# ADC_Power_supply.net
KiCad netlist of a schematic drawn in Altium Designer
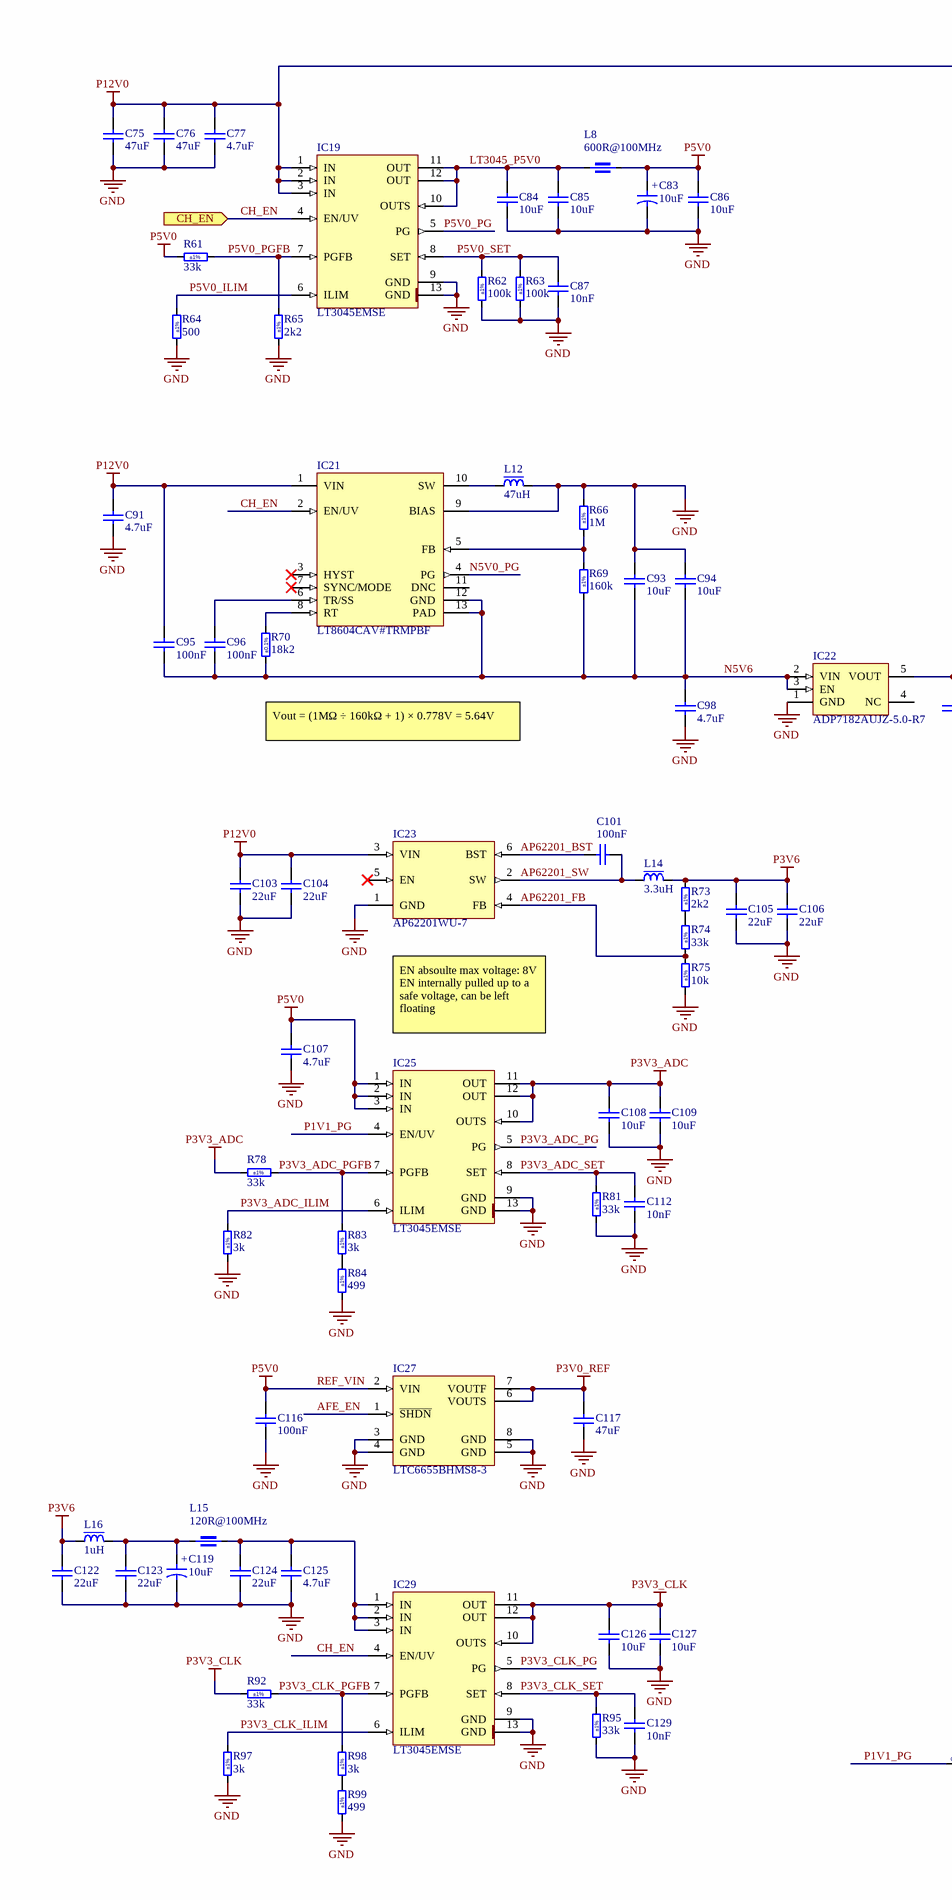
[diagram p0: ADC_Power_supply.SchDoc, left]
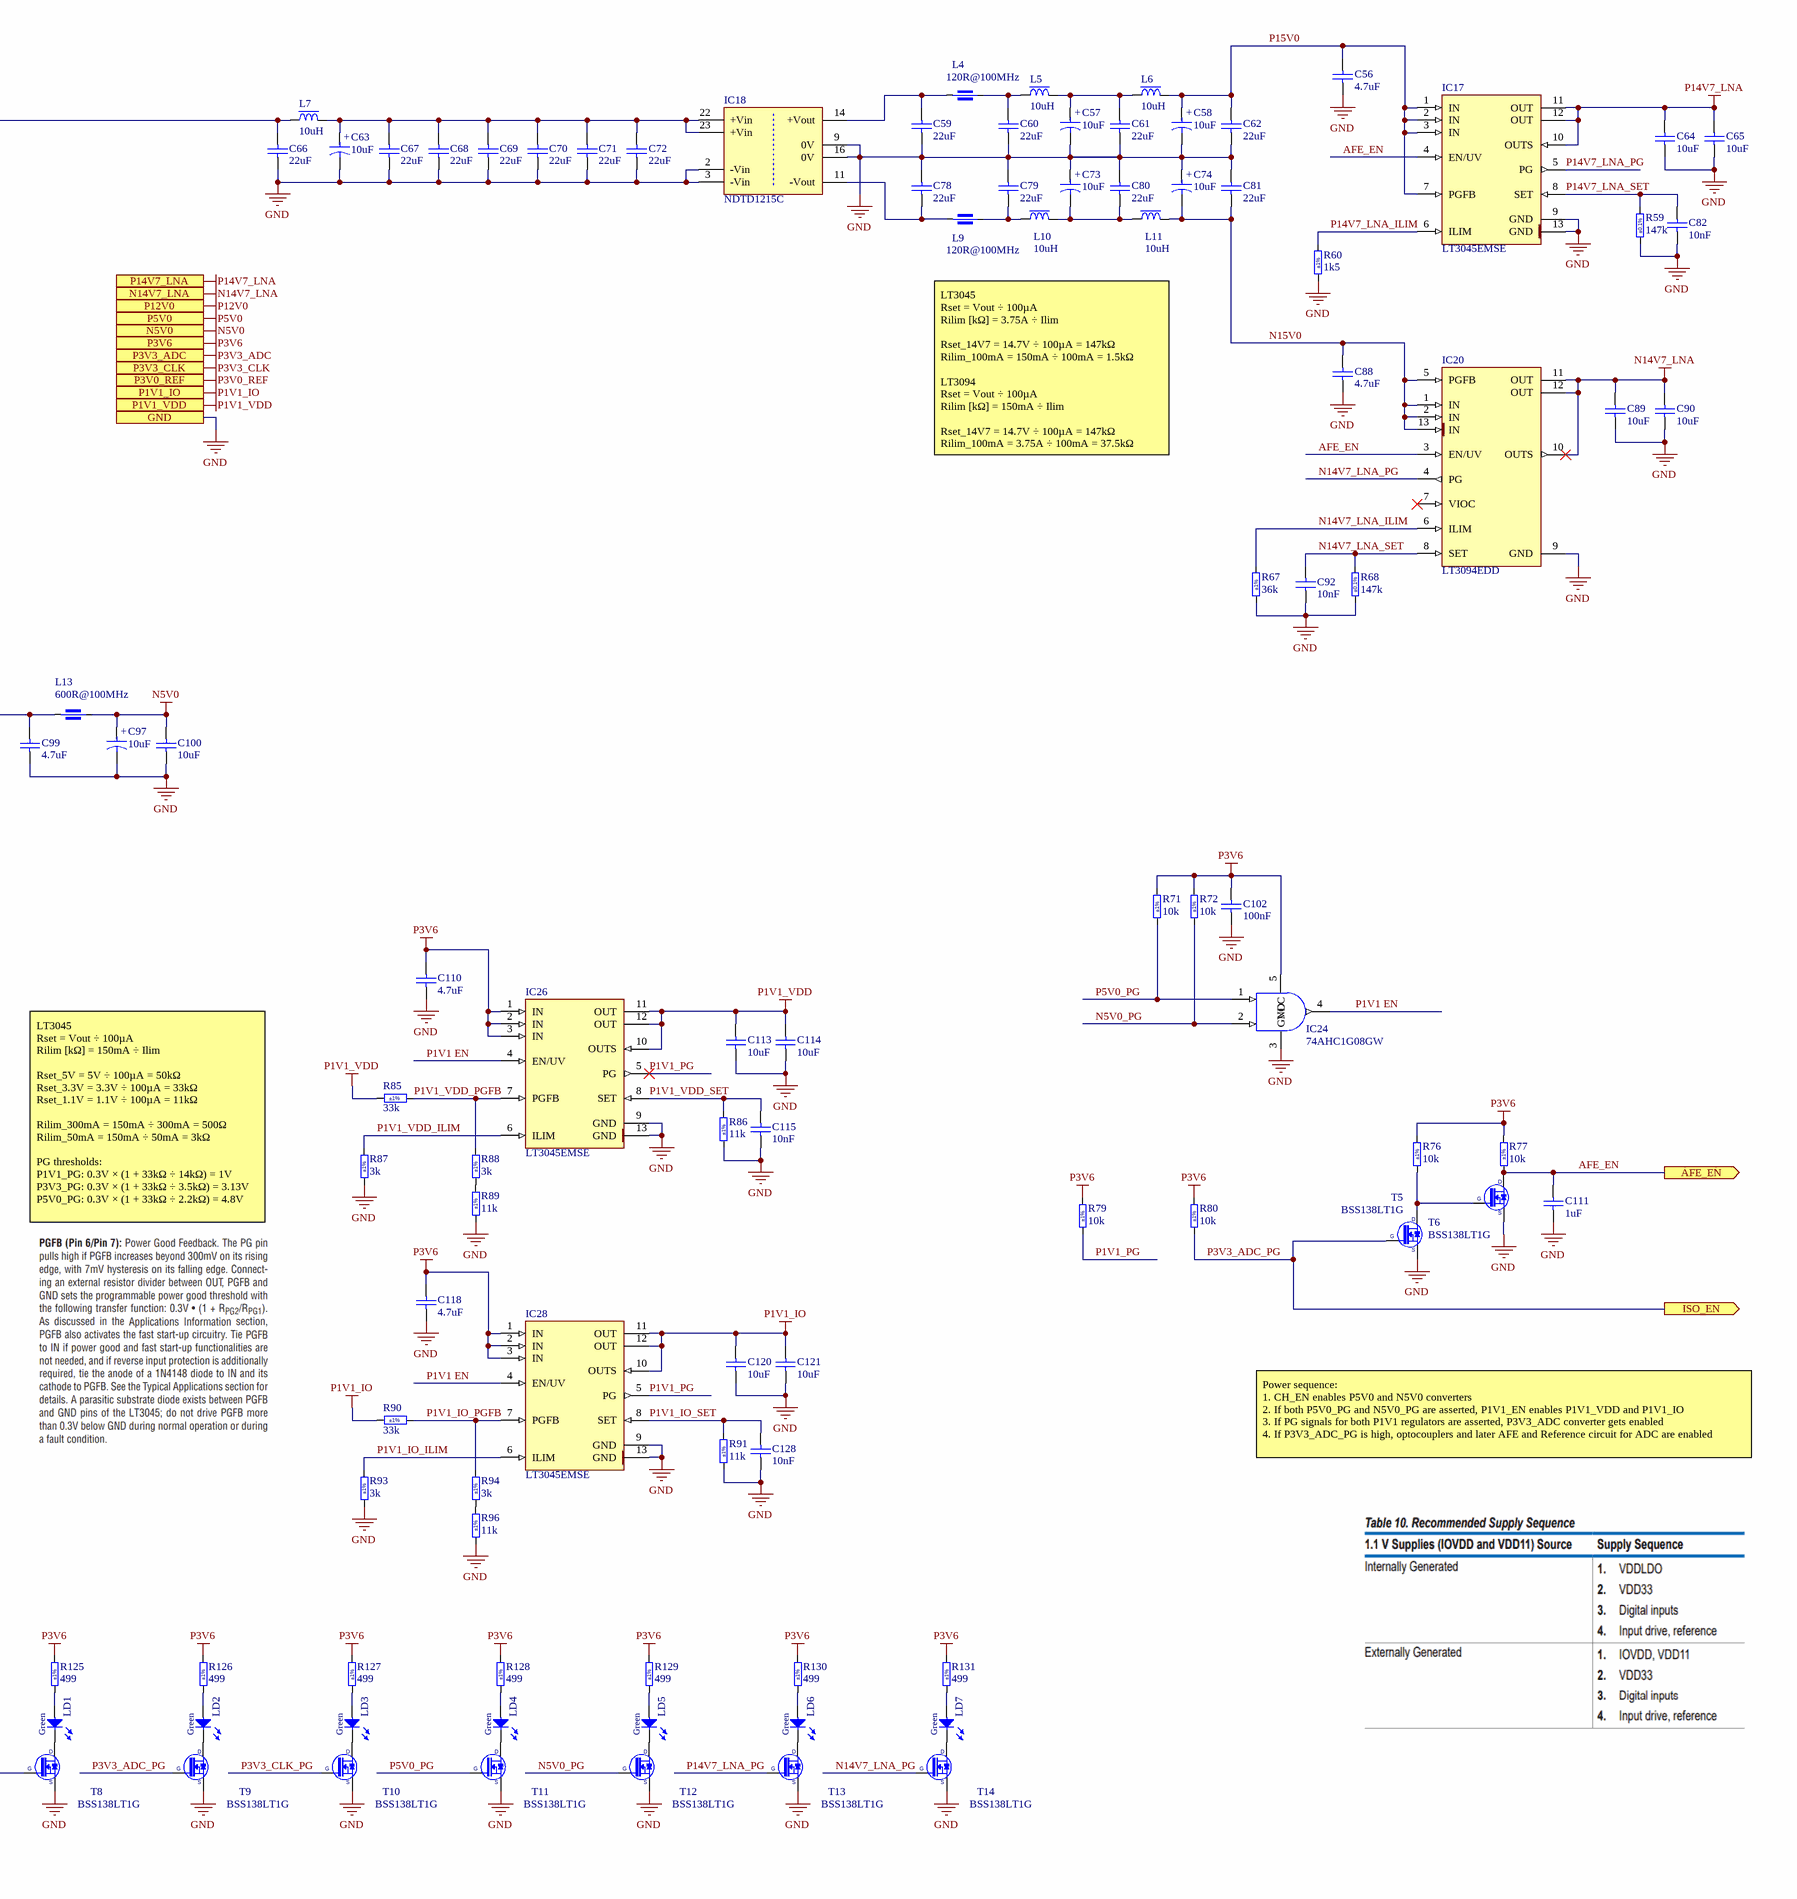
[diagram p1: ADC_Power_supply.SchDoc, right]

(export (version "E")
  (design (tool "Eeschema 10.0.6"))
  (components
    (comp (ref "C56")
      (value "4.7uF")
      (footprint "CAPC1608X90N")
      (description "Non-polarised capacitor")
      (fields
        (field (name "PART NUMBER") "CC0603_4.7UF_25V_10%_X5R")
        (field (name "VOLTAGE") "25V")
        (field (name "AUTHOR") "CERN DEM JLC")
      )
      (libsource (lib "Capacitors") (part "Capacitor - non polarized"))
    )
    (comp (ref "C57")
      (value "10uF")
      (footprint "CAPMP3216X180N")
      (description "Polarised capacitor")
      (fields
        (field (name "PART NUMBER") "CTE3216-18_10UF_16V_20%_AVX_TCJ")
        (field (name "VOLTAGE") "16V")
        (field (name "AUTHOR") "CERN DEM JLC")
      )
      (libsource (lib "Capacitors") (part "Capacitor - polarized"))
    )
    (comp (ref "C58")
      (value "10uF")
      (footprint "CAPMP3216X180N")
      (description "Polarised capacitor")
      (fields
        (field (name "PART NUMBER") "CTE3216-18_10UF_16V_20%_AVX_TCJ")
        (field (name "VOLTAGE") "16V")
        (field (name "AUTHOR") "CERN DEM JLC")
      )
      (libsource (lib "Capacitors") (part "Capacitor - polarized"))
    )
    (comp (ref "C59")
      (value "22uF")
      (footprint "CAPC2012X135N")
      (description "Non-polarised capacitor")
      (fields
        (field (name "PART NUMBER") "CC0805_22UF_16V_10%_X5R")
        (field (name "VOLTAGE") "16V")
        (field (name "AUTHOR") "CERN DEM JLC")
      )
      (libsource (lib "Capacitors") (part "Capacitor - non polarized"))
    )
    (comp (ref "C60")
      (value "22uF")
      (footprint "CAPC2012X135N")
      (description "Non-polarised capacitor")
      (fields
        (field (name "PART NUMBER") "CC0805_22UF_16V_10%_X5R")
        (field (name "VOLTAGE") "16V")
        (field (name "AUTHOR") "CERN DEM JLC")
      )
      (libsource (lib "Capacitors") (part "Capacitor - non polarized"))
    )
    (comp (ref "C61")
      (value "22uF")
      (footprint "CAPC2012X135N")
      (description "Non-polarised capacitor")
      (fields
        (field (name "PART NUMBER") "CC0805_22UF_16V_10%_X5R")
        (field (name "VOLTAGE") "16V")
        (field (name "AUTHOR") "CERN DEM JLC")
      )
      (libsource (lib "Capacitors") (part "Capacitor - non polarized"))
    )
    (comp (ref "C62")
      (value "22uF")
      (footprint "CAPC2012X135N")
      (description "Non-polarised capacitor")
      (fields
        (field (name "PART NUMBER") "CC0805_22UF_16V_10%_X5R")
        (field (name "VOLTAGE") "16V")
        (field (name "AUTHOR") "CERN DEM JLC")
      )
      (libsource (lib "Capacitors") (part "Capacitor - non polarized"))
    )
    (comp (ref "C63")
      (value "10uF")
      (footprint "CAPMP3216X180N")
      (description "Polarised capacitor")
      (fields
        (field (name "PART NUMBER") "CTE3216-18_10UF_16V_20%_AVX_TCJ")
        (field (name "VOLTAGE") "16V")
        (field (name "AUTHOR") "CERN DEM JLC")
      )
      (libsource (lib "Capacitors") (part "Capacitor - polarized"))
    )
    (comp (ref "C64")
      (value "10uF")
      (footprint "CAPC2012X95N")
      (description "Non-polarised capacitor")
      (fields
        (field (name "PART NUMBER") "CC0805_10UF_25V_10%_X5R")
        (field (name "VOLTAGE") "25V")
        (field (name "AUTHOR") "CERN DEM JLC")
      )
      (libsource (lib "Capacitors") (part "Capacitor - non polarized"))
    )
    (comp (ref "C65")
      (value "10uF")
      (footprint "CAPC2012X95N")
      (description "Non-polarised capacitor")
      (fields
        (field (name "PART NUMBER") "CC0805_10UF_25V_10%_X5R")
        (field (name "VOLTAGE") "25V")
        (field (name "AUTHOR") "CERN DEM JLC")
      )
      (libsource (lib "Capacitors") (part "Capacitor - non polarized"))
    )
    (comp (ref "C66")
      (value "22uF")
      (footprint "CAPC2012X135N")
      (description "Non-polarised capacitor")
      (fields
        (field (name "PART NUMBER") "CC0805_22UF_16V_10%_X5R")
        (field (name "VOLTAGE") "16V")
        (field (name "AUTHOR") "CERN DEM JLC")
      )
      (libsource (lib "Capacitors") (part "Capacitor - non polarized"))
    )
    (comp (ref "C67")
      (value "22uF")
      (footprint "CAPC2012X135N")
      (description "Non-polarised capacitor")
      (fields
        (field (name "PART NUMBER") "CC0805_22UF_16V_10%_X5R")
        (field (name "VOLTAGE") "16V")
        (field (name "AUTHOR") "CERN DEM JLC")
      )
      (libsource (lib "Capacitors") (part "Capacitor - non polarized"))
    )
    (comp (ref "C68")
      (value "22uF")
      (footprint "CAPC2012X135N")
      (description "Non-polarised capacitor")
      (fields
        (field (name "PART NUMBER") "CC0805_22UF_16V_10%_X5R")
        (field (name "VOLTAGE") "16V")
        (field (name "AUTHOR") "CERN DEM JLC")
      )
      (libsource (lib "Capacitors") (part "Capacitor - non polarized"))
    )
    (comp (ref "C69")
      (value "22uF")
      (footprint "CAPC2012X135N")
      (description "Non-polarised capacitor")
      (fields
        (field (name "PART NUMBER") "CC0805_22UF_16V_10%_X5R")
        (field (name "VOLTAGE") "16V")
        (field (name "AUTHOR") "CERN DEM JLC")
      )
      (libsource (lib "Capacitors") (part "Capacitor - non polarized"))
    )
    (comp (ref "C70")
      (value "22uF")
      (footprint "CAPC2012X135N")
      (description "Non-polarised capacitor")
      (fields
        (field (name "PART NUMBER") "CC0805_22UF_16V_10%_X5R")
        (field (name "VOLTAGE") "16V")
        (field (name "AUTHOR") "CERN DEM JLC")
      )
      (libsource (lib "Capacitors") (part "Capacitor - non polarized"))
    )
    (comp (ref "C71")
      (value "22uF")
      (footprint "CAPC2012X135N")
      (description "Non-polarised capacitor")
      (fields
        (field (name "PART NUMBER") "CC0805_22UF_16V_10%_X5R")
        (field (name "VOLTAGE") "16V")
        (field (name "AUTHOR") "CERN DEM JLC")
      )
      (libsource (lib "Capacitors") (part "Capacitor - non polarized"))
    )
    (comp (ref "C72")
      (value "22uF")
      (footprint "CAPC2012X135N")
      (description "Non-polarised capacitor")
      (fields
        (field (name "PART NUMBER") "CC0805_22UF_16V_10%_X5R")
        (field (name "VOLTAGE") "16V")
        (field (name "AUTHOR") "CERN DEM JLC")
      )
      (libsource (lib "Capacitors") (part "Capacitor - non polarized"))
    )
    (comp (ref "C73")
      (value "10uF")
      (footprint "CAPMP3216X180N")
      (description "Polarised capacitor")
      (fields
        (field (name "PART NUMBER") "CTE3216-18_10UF_16V_20%_AVX_TCJ")
        (field (name "VOLTAGE") "16V")
        (field (name "AUTHOR") "CERN DEM JLC")
      )
      (libsource (lib "Capacitors") (part "Capacitor - polarized"))
    )
    (comp (ref "C74")
      (value "10uF")
      (footprint "CAPMP3216X180N")
      (description "Polarised capacitor")
      (fields
        (field (name "PART NUMBER") "CTE3216-18_10UF_16V_20%_AVX_TCJ")
        (field (name "VOLTAGE") "16V")
        (field (name "AUTHOR") "CERN DEM JLC")
      )
      (libsource (lib "Capacitors") (part "Capacitor - polarized"))
    )
    (comp (ref "C75")
      (value "47uF")
      (footprint "CAPC3216X180N")
      (description "Non-polarised capacitor")
      (fields
        (field (name "PART NUMBER") "CC1206_47UF_25V_20%_X5R")
        (field (name "VOLTAGE") "25V")
        (field (name "AUTHOR") "CERN DEM JLC")
      )
      (libsource (lib "Capacitors") (part "Capacitor - non polarized"))
    )
    (comp (ref "C76")
      (value "47uF")
      (footprint "CAPC3216X180N")
      (description "Non-polarised capacitor")
      (fields
        (field (name "PART NUMBER") "CC1206_47UF_25V_20%_X5R")
        (field (name "VOLTAGE") "25V")
        (field (name "AUTHOR") "CERN DEM JLC")
      )
      (libsource (lib "Capacitors") (part "Capacitor - non polarized"))
    )
    (comp (ref "C77")
      (value "4.7uF")
      (footprint "CAPC1608X90N")
      (description "Non-polarised capacitor")
      (fields
        (field (name "PART NUMBER") "CC0603_4.7UF_25V_10%_X5R")
        (field (name "VOLTAGE") "25V")
        (field (name "AUTHOR") "CERN DEM JLC")
      )
      (libsource (lib "Capacitors") (part "Capacitor - non polarized"))
    )
    (comp (ref "C78")
      (value "22uF")
      (footprint "CAPC2012X135N")
      (description "Non-polarised capacitor")
      (fields
        (field (name "PART NUMBER") "CC0805_22UF_16V_10%_X5R")
        (field (name "VOLTAGE") "16V")
        (field (name "AUTHOR") "CERN DEM JLC")
      )
      (libsource (lib "Capacitors") (part "Capacitor - non polarized"))
    )
    (comp (ref "C79")
      (value "22uF")
      (footprint "CAPC2012X135N")
      (description "Non-polarised capacitor")
      (fields
        (field (name "PART NUMBER") "CC0805_22UF_16V_10%_X5R")
        (field (name "VOLTAGE") "16V")
        (field (name "AUTHOR") "CERN DEM JLC")
      )
      (libsource (lib "Capacitors") (part "Capacitor - non polarized"))
    )
    (comp (ref "C80")
      (value "22uF")
      (footprint "CAPC2012X135N")
      (description "Non-polarised capacitor")
      (fields
        (field (name "PART NUMBER") "CC0805_22UF_16V_10%_X5R")
        (field (name "VOLTAGE") "16V")
        (field (name "AUTHOR") "CERN DEM JLC")
      )
      (libsource (lib "Capacitors") (part "Capacitor - non polarized"))
    )
    (comp (ref "C81")
      (value "22uF")
      (footprint "CAPC2012X135N")
      (description "Non-polarised capacitor")
      (fields
        (field (name "PART NUMBER") "CC0805_22UF_16V_10%_X5R")
        (field (name "VOLTAGE") "16V")
        (field (name "AUTHOR") "CERN DEM JLC")
      )
      (libsource (lib "Capacitors") (part "Capacitor - non polarized"))
    )
    (comp (ref "C82")
      (value "10nF")
      (footprint "CAPC1005X55N")
      (description "Non-polarised capacitor")
      (fields
        (field (name "PART NUMBER") "CC0402_10NF_16V_10%_X7R")
        (field (name "VOLTAGE") "16V")
        (field (name "AUTHOR") "CERN DEM JLC")
      )
      (libsource (lib "Capacitors") (part "Capacitor - non polarized"))
    )
    (comp (ref "C83")
      (value "10uF")
      (footprint "CAPMP3216X180N")
      (description "Polarised capacitor")
      (fields
        (field (name "PART NUMBER") "CTE3216-18_10UF_10V_10%_LESR1800")
        (field (name "VOLTAGE") "10V")
        (field (name "AUTHOR") "CERN DEM JLC")
      )
      (libsource (lib "Capacitors") (part "Capacitor - polarized"))
    )
    (comp (ref "C84")
      (value "10uF")
      (footprint "CAPC2012X95N")
      (description "Non-polarised capacitor")
      (fields
        (field (name "PART NUMBER") "CC0805_10UF_25V_10%_X5R")
        (field (name "VOLTAGE") "25V")
        (field (name "AUTHOR") "CERN DEM JLC")
      )
      (libsource (lib "Capacitors") (part "Capacitor - non polarized"))
    )
    (comp (ref "C85")
      (value "10uF")
      (footprint "CAPC2012X95N")
      (description "Non-polarised capacitor")
      (fields
        (field (name "PART NUMBER") "CC0805_10UF_25V_10%_X5R")
        (field (name "VOLTAGE") "25V")
        (field (name "AUTHOR") "CERN DEM JLC")
      )
      (libsource (lib "Capacitors") (part "Capacitor - non polarized"))
    )
    (comp (ref "C86")
      (value "10uF")
      (footprint "CAPC2012X95N")
      (description "Non-polarised capacitor")
      (fields
        (field (name "PART NUMBER") "CC0805_10UF_25V_10%_X5R")
        (field (name "VOLTAGE") "25V")
        (field (name "AUTHOR") "CERN DEM JLC")
      )
      (libsource (lib "Capacitors") (part "Capacitor - non polarized"))
    )
    (comp (ref "C87")
      (value "10nF")
      (footprint "CAPC1005X55N")
      (description "Non-polarised capacitor")
      (fields
        (field (name "PART NUMBER") "CC0402_10NF_16V_10%_X7R")
        (field (name "VOLTAGE") "16V")
        (field (name "AUTHOR") "CERN DEM JLC")
      )
      (libsource (lib "Capacitors") (part "Capacitor - non polarized"))
    )
    (comp (ref "C88")
      (value "4.7uF")
      (footprint "CAPC1608X90N")
      (description "Non-polarised capacitor")
      (fields
        (field (name "PART NUMBER") "CC0603_4.7UF_25V_10%_X5R")
        (field (name "VOLTAGE") "25V")
        (field (name "AUTHOR") "CERN DEM JLC")
      )
      (libsource (lib "Capacitors") (part "Capacitor - non polarized"))
    )
    (comp (ref "C89")
      (value "10uF")
      (footprint "CAPC2012X95N")
      (description "Non-polarised capacitor")
      (fields
        (field (name "PART NUMBER") "CC0805_10UF_25V_10%_X5R")
        (field (name "VOLTAGE") "25V")
        (field (name "AUTHOR") "CERN DEM JLC")
      )
      (libsource (lib "Capacitors") (part "Capacitor - non polarized"))
    )
    (comp (ref "C90")
      (value "10uF")
      (footprint "CAPC2012X95N")
      (description "Non-polarised capacitor")
      (fields
        (field (name "PART NUMBER") "CC0805_10UF_25V_10%_X5R")
        (field (name "VOLTAGE") "25V")
        (field (name "AUTHOR") "CERN DEM JLC")
      )
      (libsource (lib "Capacitors") (part "Capacitor - non polarized"))
    )
    (comp (ref "C91")
      (value "4.7uF")
      (footprint "CAPC1608X90N")
      (description "Non-polarised capacitor")
      (fields
        (field (name "PART NUMBER") "CC0603_4.7UF_25V_10%_X5R")
        (field (name "VOLTAGE") "25V")
        (field (name "AUTHOR") "CERN DEM JLC")
      )
      (libsource (lib "Capacitors") (part "Capacitor - non polarized"))
    )
    (comp (ref "C92")
      (value "10nF")
      (footprint "CAPC1005X55N")
      (description "Non-polarised capacitor")
      (fields
        (field (name "PART NUMBER") "CC0402_10NF_16V_10%_X7R")
        (field (name "VOLTAGE") "16V")
        (field (name "AUTHOR") "CERN DEM JLC")
      )
      (libsource (lib "Capacitors") (part "Capacitor - non polarized"))
    )
    (comp (ref "C93")
      (value "10uF")
      (footprint "CAPC2012X95N")
      (description "Non-polarised capacitor")
      (fields
        (field (name "PART NUMBER") "CC0805_10UF_25V_10%_X5R")
        (field (name "VOLTAGE") "25V")
        (field (name "AUTHOR") "CERN DEM JLC")
      )
      (libsource (lib "Capacitors") (part "Capacitor - non polarized"))
    )
    (comp (ref "C94")
      (value "10uF")
      (footprint "CAPC2012X95N")
      (description "Non-polarised capacitor")
      (fields
        (field (name "PART NUMBER") "CC0805_10UF_25V_10%_X5R")
        (field (name "VOLTAGE") "25V")
        (field (name "AUTHOR") "CERN DEM JLC")
      )
      (libsource (lib "Capacitors") (part "Capacitor - non polarized"))
    )
    (comp (ref "C95")
      (value "100nF")
      (footprint "CAPC1005X55N")
      (description "Non-polarised capacitor")
      (fields
        (field (name "PART NUMBER") "CC0402_100NF_50V_10%_X7R")
        (field (name "VOLTAGE") "50V")
        (field (name "AUTHOR") "CERN DEM MR")
      )
      (libsource (lib "Capacitors") (part "Capacitor - non polarized"))
    )
    (comp (ref "C96")
      (value "100nF")
      (footprint "CAPC1005X55N")
      (description "Non-polarised capacitor")
      (fields
        (field (name "PART NUMBER") "CC0402_100NF_50V_10%_X7R")
        (field (name "VOLTAGE") "50V")
        (field (name "AUTHOR") "CERN DEM MR")
      )
      (libsource (lib "Capacitors") (part "Capacitor - non polarized"))
    )
    (comp (ref "C97")
      (value "10uF")
      (footprint "CAPMP3216X180N")
      (description "Polarised capacitor")
      (fields
        (field (name "PART NUMBER") "CTE3216-18_10UF_10V_10%_LESR1800")
        (field (name "VOLTAGE") "10V")
        (field (name "AUTHOR") "CERN DEM JLC")
      )
      (libsource (lib "Capacitors") (part "Capacitor - polarized"))
    )
    (comp (ref "C98")
      (value "4.7uF")
      (footprint "CAPC1608X90N")
      (description "Non-polarised capacitor")
      (fields
        (field (name "PART NUMBER") "CC0603_4.7UF_25V_10%_X5R")
        (field (name "VOLTAGE") "25V")
        (field (name "AUTHOR") "CERN DEM JLC")
      )
      (libsource (lib "Capacitors") (part "Capacitor - non polarized"))
    )
    (comp (ref "C99")
      (value "4.7uF")
      (footprint "CAPC1608X90N")
      (description "Non-polarised capacitor")
      (fields
        (field (name "PART NUMBER") "CC0603_4.7UF_25V_10%_X5R")
        (field (name "VOLTAGE") "25V")
        (field (name "AUTHOR") "CERN DEM JLC")
      )
      (libsource (lib "Capacitors") (part "Capacitor - non polarized"))
    )
    (comp (ref "C100")
      (value "10uF")
      (footprint "CAPC2012X95N")
      (description "Non-polarised capacitor")
      (fields
        (field (name "PART NUMBER") "CC0805_10UF_25V_10%_X5R")
        (field (name "VOLTAGE") "25V")
        (field (name "AUTHOR") "CERN DEM JLC")
      )
      (libsource (lib "Capacitors") (part "Capacitor - non polarized"))
    )
    (comp (ref "C101")
      (value "100nF")
      (footprint "CAPC1005X55N")
      (description "Non-polarised capacitor")
      (fields
        (field (name "PART NUMBER") "CC0402_100NF_16V_10%_X7R")
        (field (name "VOLTAGE") "16V")
        (field (name "AUTHOR") "CERN DEM JLC")
      )
      (libsource (lib "Capacitors") (part "Capacitor - non polarized"))
    )
    (comp (ref "C102")
      (value "100nF")
      (footprint "CAPC1005X55N")
      (description "Non-polarised capacitor")
      (fields
        (field (name "PART NUMBER") "CC0402_100NF_16V_10%_X7R")
        (field (name "VOLTAGE") "16V")
        (field (name "AUTHOR") "CERN DEM JLC")
      )
      (libsource (lib "Capacitors") (part "Capacitor - non polarized"))
    )
    (comp (ref "C103")
      (value "22uF")
      (footprint "CAPC2012X135N")
      (description "Non-polarised capacitor")
      (fields
        (field (name "PART NUMBER") "CC0805_22UF_16V_10%_X5R")
        (field (name "VOLTAGE") "16V")
        (field (name "AUTHOR") "CERN DEM JLC")
      )
      (libsource (lib "Capacitors") (part "Capacitor - non polarized"))
    )
    (comp (ref "C104")
      (value "22uF")
      (footprint "CAPC2012X135N")
      (description "Non-polarised capacitor")
      (fields
        (field (name "PART NUMBER") "CC0805_22UF_16V_10%_X5R")
        (field (name "VOLTAGE") "16V")
        (field (name "AUTHOR") "CERN DEM JLC")
      )
      (libsource (lib "Capacitors") (part "Capacitor - non polarized"))
    )
    (comp (ref "C105")
      (value "22uF")
      (footprint "CAPC2012X135N")
      (description "Non-polarised capacitor")
      (fields
        (field (name "PART NUMBER") "CC0805_22UF_16V_10%_X5R")
        (field (name "VOLTAGE") "16V")
        (field (name "AUTHOR") "CERN DEM JLC")
      )
      (libsource (lib "Capacitors") (part "Capacitor - non polarized"))
    )
    (comp (ref "C106")
      (value "22uF")
      (footprint "CAPC2012X135N")
      (description "Non-polarised capacitor")
      (fields
        (field (name "PART NUMBER") "CC0805_22UF_16V_10%_X5R")
        (field (name "VOLTAGE") "16V")
        (field (name "AUTHOR") "CERN DEM JLC")
      )
      (libsource (lib "Capacitors") (part "Capacitor - non polarized"))
    )
    (comp (ref "C107")
      (value "4.7uF")
      (footprint "CAPC1608X90N")
      (description "Non-polarised capacitor")
      (fields
        (field (name "PART NUMBER") "CC0603_4.7UF_25V_10%_X5R")
        (field (name "VOLTAGE") "25V")
        (field (name "AUTHOR") "CERN DEM JLC")
      )
      (libsource (lib "Capacitors") (part "Capacitor - non polarized"))
    )
    (comp (ref "C108")
      (value "10uF")
      (footprint "CAPC2012X95N")
      (description "Non-polarised capacitor")
      (fields
        (field (name "PART NUMBER") "CC0805_10UF_25V_10%_X5R")
        (field (name "VOLTAGE") "25V")
        (field (name "AUTHOR") "CERN DEM JLC")
      )
      (libsource (lib "Capacitors") (part "Capacitor - non polarized"))
    )
    (comp (ref "C109")
      (value "10uF")
      (footprint "CAPC2012X95N")
      (description "Non-polarised capacitor")
      (fields
        (field (name "PART NUMBER") "CC0805_10UF_25V_10%_X5R")
        (field (name "VOLTAGE") "25V")
        (field (name "AUTHOR") "CERN DEM JLC")
      )
      (libsource (lib "Capacitors") (part "Capacitor - non polarized"))
    )
    (comp (ref "C110")
      (value "4.7uF")
      (footprint "CAPC1608X90N")
      (description "Non-polarised capacitor")
      (fields
        (field (name "PART NUMBER") "CC0603_4.7UF_25V_10%_X5R")
        (field (name "VOLTAGE") "25V")
        (field (name "AUTHOR") "CERN DEM JLC")
      )
      (libsource (lib "Capacitors") (part "Capacitor - non polarized"))
    )
    (comp (ref "C111")
      (value "1uF")
      (footprint "CAPC1608X87N")
      (description "Non-polarised capacitor")
      (fields
        (field (name "PART NUMBER") "CC0603_1UF_25V_10%_X7R")
        (field (name "VOLTAGE") "25V")
        (field (name "AUTHOR") "CERN DEM JLC")
      )
      (libsource (lib "Capacitors") (part "Capacitor - non polarized"))
    )
    (comp (ref "C112")
      (value "10nF")
      (footprint "CAPC1005X55N")
      (description "Non-polarised capacitor")
      (fields
        (field (name "PART NUMBER") "CC0402_10NF_16V_10%_X7R")
        (field (name "VOLTAGE") "16V")
        (field (name "AUTHOR") "CERN DEM JLC")
      )
      (libsource (lib "Capacitors") (part "Capacitor - non polarized"))
    )
    (comp (ref "C113")
      (value "10uF")
      (footprint "CAPC2012X95N")
      (description "Non-polarised capacitor")
      (fields
        (field (name "PART NUMBER") "CC0805_10UF_25V_10%_X5R")
        (field (name "VOLTAGE") "25V")
        (field (name "AUTHOR") "CERN DEM JLC")
      )
      (libsource (lib "Capacitors") (part "Capacitor - non polarized"))
    )
    (comp (ref "C114")
      (value "10uF")
      (footprint "CAPC2012X95N")
      (description "Non-polarised capacitor")
      (fields
        (field (name "PART NUMBER") "CC0805_10UF_25V_10%_X5R")
        (field (name "VOLTAGE") "25V")
        (field (name "AUTHOR") "CERN DEM JLC")
      )
      (libsource (lib "Capacitors") (part "Capacitor - non polarized"))
    )
    (comp (ref "C115")
      (value "10nF")
      (footprint "CAPC1005X55N")
      (description "Non-polarised capacitor")
      (fields
        (field (name "PART NUMBER") "CC0402_10NF_16V_10%_X7R")
        (field (name "VOLTAGE") "16V")
        (field (name "AUTHOR") "CERN DEM JLC")
      )
      (libsource (lib "Capacitors") (part "Capacitor - non polarized"))
    )
    (comp (ref "C116")
      (value "100nF")
      (footprint "CAPC1005X55N")
      (description "Non-polarised capacitor")
      (fields
        (field (name "PART NUMBER") "CC0402_100NF_50V_10%_X7R")
        (field (name "VOLTAGE") "50V")
        (field (name "AUTHOR") "CERN DEM MR")
      )
      (libsource (lib "Capacitors") (part "Capacitor - non polarized"))
    )
    (comp (ref "C117")
      (value "47uF")
      (footprint "CAPC2012X140N")
      (description "Non-polarised capacitor")
      (fields
        (field (name "PART NUMBER") "CC0805_47UF_6.3V_10%_X5R")
        (field (name "VOLTAGE") "6.3V")
        (field (name "AUTHOR") "CERN DEM HF")
      )
      (libsource (lib "Capacitors") (part "Capacitor - non polarized"))
    )
    (comp (ref "C118")
      (value "4.7uF")
      (footprint "CAPC1608X90N")
      (description "Non-polarised capacitor")
      (fields
        (field (name "PART NUMBER") "CC0603_4.7UF_25V_10%_X5R")
        (field (name "VOLTAGE") "25V")
        (field (name "AUTHOR") "CERN DEM JLC")
      )
      (libsource (lib "Capacitors") (part "Capacitor - non polarized"))
    )
    (comp (ref "C119")
      (value "10uF")
      (footprint "CAPMP3216X180N")
      (description "Polarised capacitor")
      (fields
        (field (name "PART NUMBER") "CTE3216-18_10UF_16V_20%_AVX_TCJ")
        (field (name "VOLTAGE") "16V")
        (field (name "AUTHOR") "CERN DEM JLC")
      )
      (libsource (lib "Capacitors") (part "Capacitor - polarized"))
    )
    (comp (ref "C120")
      (value "10uF")
      (footprint "CAPC2012X95N")
      (description "Non-polarised capacitor")
      (fields
        (field (name "PART NUMBER") "CC0805_10UF_25V_10%_X5R")
        (field (name "VOLTAGE") "25V")
        (field (name "AUTHOR") "CERN DEM JLC")
      )
      (libsource (lib "Capacitors") (part "Capacitor - non polarized"))
    )
    (comp (ref "C121")
      (value "10uF")
      (footprint "CAPC2012X95N")
      (description "Non-polarised capacitor")
      (fields
        (field (name "PART NUMBER") "CC0805_10UF_25V_10%_X5R")
        (field (name "VOLTAGE") "25V")
        (field (name "AUTHOR") "CERN DEM JLC")
      )
      (libsource (lib "Capacitors") (part "Capacitor - non polarized"))
    )
    (comp (ref "C122")
      (value "22uF")
      (footprint "CAPC2012X135N")
      (description "Non-polarised capacitor")
      (fields
        (field (name "PART NUMBER") "CC0805_22UF_16V_10%_X5R")
        (field (name "VOLTAGE") "16V")
        (field (name "AUTHOR") "CERN DEM JLC")
      )
      (libsource (lib "Capacitors") (part "Capacitor - non polarized"))
    )
    (comp (ref "C123")
      (value "22uF")
      (footprint "CAPC2012X135N")
      (description "Non-polarised capacitor")
      (fields
        (field (name "PART NUMBER") "CC0805_22UF_16V_10%_X5R")
        (field (name "VOLTAGE") "16V")
        (field (name "AUTHOR") "CERN DEM JLC")
      )
      (libsource (lib "Capacitors") (part "Capacitor - non polarized"))
    )
    (comp (ref "C124")
      (value "22uF")
      (footprint "CAPC2012X135N")
      (description "Non-polarised capacitor")
      (fields
        (field (name "PART NUMBER") "CC0805_22UF_16V_10%_X5R")
        (field (name "VOLTAGE") "16V")
        (field (name "AUTHOR") "CERN DEM JLC")
      )
      (libsource (lib "Capacitors") (part "Capacitor - non polarized"))
    )
    (comp (ref "C125")
      (value "4.7uF")
      (footprint "CAPC1608X90N")
      (description "Non-polarised capacitor")
      (fields
        (field (name "PART NUMBER") "CC0603_4.7UF_25V_10%_X5R")
        (field (name "VOLTAGE") "25V")
        (field (name "AUTHOR") "CERN DEM JLC")
      )
      (libsource (lib "Capacitors") (part "Capacitor - non polarized"))
    )
    (comp (ref "C126")
      (value "10uF")
      (footprint "CAPC2012X95N")
      (description "Non-polarised capacitor")
      (fields
        (field (name "PART NUMBER") "CC0805_10UF_25V_10%_X5R")
        (field (name "VOLTAGE") "25V")
        (field (name "AUTHOR") "CERN DEM JLC")
      )
      (libsource (lib "Capacitors") (part "Capacitor - non polarized"))
    )
    (comp (ref "C127")
      (value "10uF")
      (footprint "CAPC2012X95N")
      (description "Non-polarised capacitor")
      (fields
        (field (name "PART NUMBER") "CC0805_10UF_25V_10%_X5R")
        (field (name "VOLTAGE") "25V")
        (field (name "AUTHOR") "CERN DEM JLC")
      )
      (libsource (lib "Capacitors") (part "Capacitor - non polarized"))
    )
    (comp (ref "C128")
      (value "10nF")
      (footprint "CAPC1005X55N")
      (description "Non-polarised capacitor")
      (fields
        (field (name "PART NUMBER") "CC0402_10NF_16V_10%_X7R")
        (field (name "VOLTAGE") "16V")
        (field (name "AUTHOR") "CERN DEM JLC")
      )
      (libsource (lib "Capacitors") (part "Capacitor - non polarized"))
    )
    (comp (ref "C129")
      (value "10nF")
      (footprint "CAPC1005X55N")
      (description "Non-polarised capacitor")
      (fields
        (field (name "PART NUMBER") "CC0402_10NF_16V_10%_X7R")
        (field (name "VOLTAGE") "16V")
        (field (name "AUTHOR") "CERN DEM JLC")
      )
      (libsource (lib "Capacitors") (part "Capacitor - non polarized"))
    )
    (comp (ref "IC17")
      (value "LT3045EMSE")
      (footprint "SOP65P490X110-13N-R175X294")
      (description "20V, 500mA, Ultralow Noise, Ultrahigh PSRR Linear Regulator")
      (fields (field (name "MANUFACTURER") "LINEAR TECHNOLOGY") (field (name "AUTHOR") "CERN DEM HF"))
      (libsource (lib "ICs And Semiconductors") (part "LT3045"))
    )
    (comp (ref "IC18")
      (value "NDTD1215C")
      (footprint "DCDC_MURATA_NDTD")
      (description "Isolated 3W Wide Input Dual Output DC-DC Converters")
      (fields (field (name "MANUFACTURER") "MURATA POWER SOLUTIONS") (field (name "AUTHOR") "CERN DEM HF"))
      (libsource (lib "ICs And Semiconductors") (part "DCDC_MURATA_NDTD"))
    )
    (comp (ref "IC19")
      (value "LT3045EMSE")
      (footprint "SOP65P490X110-13N-R175X294")
      (description "20V, 500mA, Ultralow Noise, Ultrahigh PSRR Linear Regulator")
      (fields (field (name "MANUFACTURER") "LINEAR TECHNOLOGY") (field (name "AUTHOR") "CERN DEM HF"))
      (libsource (lib "ICs And Semiconductors") (part "LT3045"))
    )
    (comp (ref "IC20")
      (value "LT3094EDD")
      (footprint "SON45P300X300X80-13N-R175X248")
      (description "-20V, 500mA, Ultralow Noise, Ultrahigh PSRR Negative Linear Regulator")
      (fields
        (field (name "PART NUMBER") "LT3094EDD#PBF")
        (field (name "MANUFACTURER") "LINEAR TECHNOLOGY")
        (field (name "AUTHOR") "CERN DEM JLC")
      )
      (libsource (lib "ICs And Semiconductors") (part "LT3094"))
    )
    (comp (ref "IC21")
      (value "LT8604CAV#TRMPBF")
      (footprint "QFN50P200X200X83_HS-13N")
      (description "High Efficiency 42V/120mA Synchronous Buck")
      (fields (field (name "MANUFACTURER") "Analog Devices") (field (name "AUTHOR") "Michal Beldyga"))
      (libsource (lib "Semiconductors") (part "LT8604C"))
    )
    (comp (ref "IC22")
      (value "ADP7182AUJZ-5.0-R7")
      (footprint "SOT95P280X90-5N")
      (description "–5V, 200 mA, Low Noise, Linear Regulator")
      (fields
        (field (name "MANUFACTURER") "ANALOG DEVICES")
        (field (name "MANUFACTURER PART NUMBER") "ADP7182AUJZ-5.0")
        (field (name "AUTHOR") "CERN DEM JLC")
      )
      (libsource (lib "ICs And Semiconductors") (part "ADP7182AUJZ-X.X-R7"))
    )
    (comp (ref "IC23")
      (value "AP62201WU-7")
      (footprint "SOT95P280X100-6N")
      (description "4.2V TO 18V INPUT, 2A LOW IQ SYNCHRONOUS BUCK CONVERTER")
      (fields
        (field (name "MANUFACTURER") "DIODES INCORPORATED")
        (field (name "MANUFACTURER PART NUMBER") "AP62201WU")
        (field (name "AUTHOR") "CERN DEM HF")
      )
      (libsource (lib "ICs And Semiconductors") (part "AP62201WU"))
    )
    (comp (ref "IC24")
      (value "74AHC1G08GW")
      (footprint "SOT65P212X110-5N")
      (description "Single 2-Input AND Gate")
      (fields (field (name "MANUFACTURER") "NXP Semiconductors") (field (name "AUTHOR") "Michal Beldyga"))
      (libsource (lib "Semiconductors") (part "741G08"))
    )
    (comp (ref "IC25")
      (value "LT3045EMSE")
      (footprint "SOP65P490X110-13N-R175X294")
      (description "20V, 500mA, Ultralow Noise, Ultrahigh PSRR Linear Regulator")
      (fields (field (name "MANUFACTURER") "LINEAR TECHNOLOGY") (field (name "AUTHOR") "CERN DEM HF"))
      (libsource (lib "ICs And Semiconductors") (part "LT3045"))
    )
    (comp (ref "IC26")
      (value "LT3045EMSE")
      (footprint "SOP65P490X110-13N-R175X294")
      (description "20V, 500mA, Ultralow Noise, Ultrahigh PSRR Linear Regulator")
      (fields (field (name "MANUFACTURER") "LINEAR TECHNOLOGY") (field (name "AUTHOR") "CERN DEM HF"))
      (libsource (lib "ICs And Semiconductors") (part "LT3045"))
    )
    (comp (ref "IC27")
      (value "LTC6655BHMS8-3")
      (footprint "SOP65P490X110-8N")
      (description "0.25ppm Noise, Low Drift Precision Buffered Voltage Reference")
      (fields (field (name "MANUFACTURER") "ANALOG DEVICES") (field (name "AUTHOR") "CERN DEM HF"))
      (libsource (lib "ICs And Semiconductors") (part "LTC6655"))
    )
    (comp (ref "IC28")
      (value "LT3045EMSE")
      (footprint "SOP65P490X110-13N-R175X294")
      (description "20V, 500mA, Ultralow Noise, Ultrahigh PSRR Linear Regulator")
      (fields (field (name "MANUFACTURER") "LINEAR TECHNOLOGY") (field (name "AUTHOR") "CERN DEM HF"))
      (libsource (lib "ICs And Semiconductors") (part "LT3045"))
    )
    (comp (ref "IC29")
      (value "LT3045EMSE")
      (footprint "SOP65P490X110-13N-R175X294")
      (description "20V, 500mA, Ultralow Noise, Ultrahigh PSRR Linear Regulator")
      (fields (field (name "MANUFACTURER") "LINEAR TECHNOLOGY") (field (name "AUTHOR") "CERN DEM HF"))
      (libsource (lib "ICs And Semiconductors") (part "LT3045"))
    )
    (comp (ref "L4")
      (value "120R@100MHz")
      (footprint "INDC1608X95N")
      (fields
        (field (name "PART NUMBER") "IND0603_MURATA_BLM18PG121SN1D")
        (field (name "POWER") "2A")
        (field (name "MANUFACTURER") "MURATA")
        (field (name "AUTHOR") "CERN DEM BC")
      )
      (libsource (lib "Inductors & Transformers") (part "Ferrite Bead"))
    )
    (comp (ref "L5")
      (value "10uH")
      (footprint "IND_MURATA-PS_8400")
      (description "Inductor With Core")
      (fields
        (field (name "PART NUMBER") "IND_10UH_10%_MURATA-PS_8400")
        (field (name "POWER") "950mA")
        (field (name "AUTHOR") "CERN DEM JLC")
      )
      (libsource (lib "Inductors & Transformers") (part "Inductor With Magnetic core"))
    )
    (comp (ref "L6")
      (value "10uH")
      (footprint "IND_MURATA-PS_8400")
      (description "Inductor With Core")
      (fields
        (field (name "PART NUMBER") "IND_10UH_10%_MURATA-PS_8400")
        (field (name "POWER") "950mA")
        (field (name "AUTHOR") "CERN DEM JLC")
      )
      (libsource (lib "Inductors & Transformers") (part "Inductor With Magnetic core"))
    )
    (comp (ref "L7")
      (value "10uH")
      (footprint "IND_MURATA-PS_8400")
      (description "Inductor With Core")
      (fields
        (field (name "PART NUMBER") "IND_10UH_10%_MURATA-PS_8400")
        (field (name "POWER") "950mA")
        (field (name "AUTHOR") "CERN DEM JLC")
      )
      (libsource (lib "Inductors & Transformers") (part "Inductor With Magnetic core"))
    )
    (comp (ref "L8")
      (value "600R@100MHz")
      (footprint "INDC1608X95N")
      (fields
        (field (name "PART NUMBER") "IND0603_MURATA_BLM18BD601SN1D")
        (field (name "POWER") "200mA")
        (field (name "TOLERANCE") "±25%")
        (field (name "AUTHOR") "CERN DEM JLC")
      )
      (libsource (lib "Inductors & Transformers") (part "Ferrite Bead"))
    )
    (comp (ref "L9")
      (value "120R@100MHz")
      (footprint "INDC1608X95N")
      (fields
        (field (name "PART NUMBER") "IND0603_MURATA_BLM18PG121SN1D")
        (field (name "POWER") "2A")
        (field (name "MANUFACTURER") "MURATA")
        (field (name "AUTHOR") "CERN DEM BC")
      )
      (libsource (lib "Inductors & Transformers") (part "Ferrite Bead"))
    )
    (comp (ref "L10")
      (value "10uH")
      (footprint "IND_MURATA-PS_8400")
      (description "Inductor With Core")
      (fields
        (field (name "PART NUMBER") "IND_10UH_10%_MURATA-PS_8400")
        (field (name "POWER") "950mA")
        (field (name "AUTHOR") "CERN DEM JLC")
      )
      (libsource (lib "Inductors & Transformers") (part "Inductor With Magnetic core"))
    )
    (comp (ref "L11")
      (value "10uH")
      (footprint "IND_MURATA-PS_8400")
      (description "Inductor With Core")
      (fields
        (field (name "PART NUMBER") "IND_10UH_10%_MURATA-PS_8400")
        (field (name "POWER") "950mA")
        (field (name "AUTHOR") "CERN DEM JLC")
      )
      (libsource (lib "Inductors & Transformers") (part "Inductor With Magnetic core"))
    )
    (comp (ref "L12")
      (value "47uH")
      (footprint "IND_NIC_NPIS64D")
      (description "Inductor With Core")
      (fields
        (field (name "PART NUMBER") "IND_47UH_20%_NIC_NPIS64D470MTRF")
        (field (name "POWER") "950mA")
        (field (name "AUTHOR") "CERN DEM JLC")
      )
      (libsource (lib "Inductors & Transformers") (part "Inductor With Magnetic core"))
    )
    (comp (ref "L13")
      (value "600R@100MHz")
      (footprint "INDC1608X95N")
      (fields
        (field (name "PART NUMBER") "IND0603_MURATA_BLM18BD601SN1D")
        (field (name "POWER") "200mA")
        (field (name "TOLERANCE") "±25%")
        (field (name "AUTHOR") "CERN DEM JLC")
      )
      (libsource (lib "Inductors & Transformers") (part "Ferrite Bead"))
    )
    (comp (ref "L14")
      (value "3.3uH")
      (footprint "IND_WURTH_WE-TPC_4828")
      (description "Inductor With Core")
      (fields
        (field (name "PART NUMBER") "IND_3.3UH_30%_WURTH_WE-TPC_744043003")
        (field (name "POWER") "2.15A")
        (field (name "AUTHOR") "CERN DEM JLC")
      )
      (libsource (lib "Inductors & Transformers") (part "Inductor With Magnetic core"))
    )
    (comp (ref "L15")
      (value "120R@100MHz")
      (footprint "INDC1608X65N")
      (fields
        (field (name "PART NUMBER") "IND0603_MURATA_BLM18SG121TN1D")
        (field (name "POWER") "3A")
        (field (name "TOLERANCE") "±25%")
        (field (name "AUTHOR") "CERN DEM JLC")
      )
      (libsource (lib "Inductors & Transformers") (part "Ferrite Bead"))
    )
    (comp (ref "L16")
      (value "1uH")
      (footprint "IND_COILCRAFT_PFL3215")
      (description "Inductor With Core")
      (fields
        (field (name "PART NUMBER") "IND_1UH_20%_COILCRAFT_PFL3215")
        (field (name "POWER") "1.9A")
        (field (name "AUTHOR") "CERN DEM MR")
      )
      (libsource (lib "Inductors & Transformers") (part "Inductor With Magnetic core"))
    )
    (comp (ref "LD1")
      (value "Green")
      (footprint "LED_AVAGO_HSME-C120")
      (description "LED Green 1C 2A")
      (fields
        (field (name "PART NUMBER") "LED_AVAGO_HSME-C120")
        (field (name "MANUFACTURER") "AVAGO TECHNOLOGIES")
        (field (name "AUTHOR") "CERN DEM JMW")
      )
      (libsource (lib "ICs And Semiconductors") (part "LED Green 1C 2A"))
    )
    (comp (ref "LD2")
      (value "Green")
      (footprint "LED_AVAGO_HSME-C120")
      (description "LED Green 1C 2A")
      (fields
        (field (name "PART NUMBER") "LED_AVAGO_HSME-C120")
        (field (name "MANUFACTURER") "AVAGO TECHNOLOGIES")
        (field (name "AUTHOR") "CERN DEM JMW")
      )
      (libsource (lib "ICs And Semiconductors") (part "LED Green 1C 2A"))
    )
    (comp (ref "LD3")
      (value "Green")
      (footprint "LED_AVAGO_HSME-C120")
      (description "LED Green 1C 2A")
      (fields
        (field (name "PART NUMBER") "LED_AVAGO_HSME-C120")
        (field (name "MANUFACTURER") "AVAGO TECHNOLOGIES")
        (field (name "AUTHOR") "CERN DEM JMW")
      )
      (libsource (lib "ICs And Semiconductors") (part "LED Green 1C 2A"))
    )
    (comp (ref "LD4")
      (value "Green")
      (footprint "LED_AVAGO_HSME-C120")
      (description "LED Green 1C 2A")
      (fields
        (field (name "PART NUMBER") "LED_AVAGO_HSME-C120")
        (field (name "MANUFACTURER") "AVAGO TECHNOLOGIES")
        (field (name "AUTHOR") "CERN DEM JMW")
      )
      (libsource (lib "ICs And Semiconductors") (part "LED Green 1C 2A"))
    )
    (comp (ref "LD5")
      (value "Green")
      (footprint "LED_AVAGO_HSME-C120")
      (description "LED Green 1C 2A")
      (fields
        (field (name "PART NUMBER") "LED_AVAGO_HSME-C120")
        (field (name "MANUFACTURER") "AVAGO TECHNOLOGIES")
        (field (name "AUTHOR") "CERN DEM JMW")
      )
      (libsource (lib "ICs And Semiconductors") (part "LED Green 1C 2A"))
    )
    (comp (ref "LD6")
      (value "Green")
      (footprint "LED_AVAGO_HSME-C120")
      (description "LED Green 1C 2A")
      (fields
        (field (name "PART NUMBER") "LED_AVAGO_HSME-C120")
        (field (name "MANUFACTURER") "AVAGO TECHNOLOGIES")
        (field (name "AUTHOR") "CERN DEM JMW")
      )
      (libsource (lib "ICs And Semiconductors") (part "LED Green 1C 2A"))
    )
    (comp (ref "LD7")
      (value "Green")
      (footprint "LED_AVAGO_HSME-C120")
      (description "LED Green 1C 2A")
      (fields
        (field (name "PART NUMBER") "LED_AVAGO_HSME-C120")
        (field (name "MANUFACTURER") "AVAGO TECHNOLOGIES")
        (field (name "AUTHOR") "CERN DEM JMW")
      )
      (libsource (lib "ICs And Semiconductors") (part "LED Green 1C 2A"))
    )
    (comp (ref "R59")
      (value "147k")
      (footprint "RESC1608X55N")
      (description "Resistor - 0.1%")
      (fields
        (field (name "TOLERANCE") "±0.1%")
        (field (name "PART NUMBER") "R0603_147K_0.1%_0.063W_10PPM")
        (field (name "POWER") "0.063W")
        (field (name "AUTHOR") "CERN DEM JLC")
      )
      (libsource (lib "Resistors") (part "Resistor - 0.1%"))
    )
    (comp (ref "R60")
      (value "1k5")
      (footprint "RESC1005X40N")
      (description "Resistor - 1%")
      (fields
        (field (name "TOLERANCE") "±1%")
        (field (name "PART NUMBER") "R0402_1K5_1%_0.0625W_100PPM")
        (field (name "POWER") "0.0625W")
        (field (name "AUTHOR") "CERN DEM JLC")
      )
      (libsource (lib "Resistors") (part "Resistor - 1%"))
    )
    (comp (ref "R61")
      (value "33k")
      (footprint "RESC1005X40N")
      (description "Resistor - 1%")
      (fields
        (field (name "TOLERANCE") "±1%")
        (field (name "PART NUMBER") "R0402_33K_1%_0.0625W_100PPM")
        (field (name "POWER") "0.0625W")
        (field (name "AUTHOR") "CERN DEM JLC")
      )
      (libsource (lib "Resistors") (part "Resistor - 1%"))
    )
    (comp (ref "R62")
      (value "100k")
      (footprint "RESC1005X40N")
      (description "Resistor - 1%")
      (fields
        (field (name "TOLERANCE") "±1%")
        (field (name "PART NUMBER") "R0402_100K_1%_0.0625W_100PPM")
        (field (name "POWER") "0.0625W")
        (field (name "AUTHOR") "CERN DEM JLC")
      )
      (libsource (lib "Resistors") (part "Resistor - 1%"))
    )
    (comp (ref "R63")
      (value "100k")
      (footprint "RESC1005X40N")
      (description "Resistor - 1%")
      (fields
        (field (name "TOLERANCE") "±1%")
        (field (name "PART NUMBER") "R0402_100K_1%_0.0625W_100PPM")
        (field (name "POWER") "0.0625W")
        (field (name "AUTHOR") "CERN DEM JLC")
      )
      (libsource (lib "Resistors") (part "Resistor - 1%"))
    )
    (comp (ref "R64")
      (value "500")
      (footprint "RESC1608X55N")
      (description "Resistor - 1%")
      (fields
        (field (name "TOLERANCE") "±1%")
        (field (name "PART NUMBER") "R0603_500R_1%_0.1W_100PPM")
        (field (name "POWER") "0.1W")
        (field (name "AUTHOR") "CERN DEM JLC")
      )
      (libsource (lib "Resistors") (part "Resistor - 1%"))
    )
    (comp (ref "R65")
      (value "2k2")
      (footprint "RESC1005X40N")
      (description "Resistor - 1%")
      (fields
        (field (name "TOLERANCE") "±1%")
        (field (name "PART NUMBER") "R0402_2K2_1%_0.0625W_100PPM")
        (field (name "POWER") "0.0625W")
        (field (name "AUTHOR") "CERN DEM JLC")
      )
      (libsource (lib "Resistors") (part "Resistor - 1%"))
    )
    (comp (ref "R66")
      (value "1M")
      (footprint "RESC1005X40N")
      (description "Resistor - 1%")
      (fields
        (field (name "TOLERANCE") "±1%")
        (field (name "PART NUMBER") "R0402_1M_1%_0.0625W_100PPM")
        (field (name "POWER") "0.0625W")
        (field (name "AUTHOR") "CERN DEM JLC")
      )
      (libsource (lib "Resistors") (part "Resistor - 1%"))
    )
    (comp (ref "R67")
      (value "36k")
      (footprint "RESC1005X40N")
      (description "Resistor - 1%")
      (fields
        (field (name "TOLERANCE") "±1%")
        (field (name "PART NUMBER") "R0402_36K_1%_0.0625W_100PPM")
        (field (name "POWER") "0.0625W")
        (field (name "AUTHOR") "CERN DEM JLC")
      )
      (libsource (lib "Resistors") (part "Resistor - 1%"))
    )
    (comp (ref "R68")
      (value "147k")
      (footprint "RESC1608X55N")
      (description "Resistor - 0.1%")
      (fields
        (field (name "TOLERANCE") "±0.1%")
        (field (name "PART NUMBER") "R0603_147K_0.1%_0.063W_10PPM")
        (field (name "POWER") "0.063W")
        (field (name "AUTHOR") "CERN DEM JLC")
      )
      (libsource (lib "Resistors") (part "Resistor - 0.1%"))
    )
    (comp (ref "R69")
      (value "160k")
      (footprint "RESC1005X40N")
      (description "Resistor - 1%")
      (fields
        (field (name "TOLERANCE") "±1%")
        (field (name "PART NUMBER") "R0402_160K_1%_0.0625W_100PPM")
        (field (name "POWER") "0.0625W")
        (field (name "AUTHOR") "CERN DEM JLC")
      )
      (libsource (lib "Resistors") (part "Resistor - 1%"))
    )
    (comp (ref "R70")
      (value "18k2")
      (footprint "RESC1608X55N")
      (description "Resistor - 0.1%")
      (fields
        (field (name "TOLERANCE") "±0.1%")
        (field (name "PART NUMBER") "R0603_18K2_0.1%_0.063W_10PPM")
        (field (name "POWER") "0.063W")
        (field (name "AUTHOR") "CERN DEM JLC")
      )
      (libsource (lib "Resistors") (part "Resistor - 0.1%"))
    )
    (comp (ref "R71")
      (value "10k")
      (footprint "RESC1005X40N")
      (description "Resistor - 1%")
      (fields
        (field (name "TOLERANCE") "±1%")
        (field (name "PART NUMBER") "R0402_10K_1%_0.0625W_100PPM")
        (field (name "POWER") "0.0625W")
        (field (name "AUTHOR") "CERN DEM JLC")
      )
      (libsource (lib "Resistors") (part "Resistor - 1%"))
    )
    (comp (ref "R72")
      (value "10k")
      (footprint "RESC1005X40N")
      (description "Resistor - 1%")
      (fields
        (field (name "TOLERANCE") "±1%")
        (field (name "PART NUMBER") "R0402_10K_1%_0.0625W_100PPM")
        (field (name "POWER") "0.0625W")
        (field (name "AUTHOR") "CERN DEM JLC")
      )
      (libsource (lib "Resistors") (part "Resistor - 1%"))
    )
    (comp (ref "R73")
      (value "2k2")
      (footprint "RESC1005X40N")
      (description "Resistor - 1%")
      (fields
        (field (name "TOLERANCE") "±1%")
        (field (name "PART NUMBER") "R0402_2K2_1%_0.0625W_100PPM")
        (field (name "POWER") "0.0625W")
        (field (name "AUTHOR") "CERN DEM JLC")
      )
      (libsource (lib "Resistors") (part "Resistor - 1%"))
    )
    (comp (ref "R74")
      (value "33k")
      (footprint "RESC1005X40N")
      (description "Resistor - 1%")
      (fields
        (field (name "TOLERANCE") "±1%")
        (field (name "PART NUMBER") "R0402_33K_1%_0.0625W_100PPM")
        (field (name "POWER") "0.0625W")
        (field (name "AUTHOR") "CERN DEM JLC")
      )
      (libsource (lib "Resistors") (part "Resistor - 1%"))
    )
    (comp (ref "R75")
      (value "10k")
      (footprint "RESC1005X40N")
      (description "Resistor - 1%")
      (fields
        (field (name "TOLERANCE") "±1%")
        (field (name "PART NUMBER") "R0402_10K_1%_0.0625W_100PPM")
        (field (name "POWER") "0.0625W")
        (field (name "AUTHOR") "CERN DEM JLC")
      )
      (libsource (lib "Resistors") (part "Resistor - 1%"))
    )
    (comp (ref "R76")
      (value "10k")
      (footprint "RESC1005X40N")
      (description "Resistor - 1%")
      (fields
        (field (name "TOLERANCE") "±1%")
        (field (name "PART NUMBER") "R0402_10K_1%_0.0625W_100PPM")
        (field (name "POWER") "0.0625W")
        (field (name "AUTHOR") "CERN DEM JLC")
      )
      (libsource (lib "Resistors") (part "Resistor - 1%"))
    )
    (comp (ref "R77")
      (value "10k")
      (footprint "RESC1005X40N")
      (description "Resistor - 1%")
      (fields
        (field (name "TOLERANCE") "±1%")
        (field (name "PART NUMBER") "R0402_10K_1%_0.0625W_100PPM")
        (field (name "POWER") "0.0625W")
        (field (name "AUTHOR") "CERN DEM JLC")
      )
      (libsource (lib "Resistors") (part "Resistor - 1%"))
    )
    (comp (ref "R78")
      (value "33k")
      (footprint "RESC1005X40N")
      (description "Resistor - 1%")
      (fields
        (field (name "TOLERANCE") "±1%")
        (field (name "PART NUMBER") "R0402_33K_1%_0.0625W_100PPM")
        (field (name "POWER") "0.0625W")
        (field (name "AUTHOR") "CERN DEM JLC")
      )
      (libsource (lib "Resistors") (part "Resistor - 1%"))
    )
    (comp (ref "R79")
      (value "10k")
      (footprint "RESC1005X40N")
      (description "Resistor - 1%")
      (fields
        (field (name "TOLERANCE") "±1%")
        (field (name "PART NUMBER") "R0402_10K_1%_0.0625W_100PPM")
        (field (name "POWER") "0.0625W")
        (field (name "AUTHOR") "CERN DEM JLC")
      )
      (libsource (lib "Resistors") (part "Resistor - 1%"))
    )
    (comp (ref "R80")
      (value "10k")
      (footprint "RESC1005X40N")
      (description "Resistor - 1%")
      (fields
        (field (name "TOLERANCE") "±1%")
        (field (name "PART NUMBER") "R0402_10K_1%_0.0625W_100PPM")
        (field (name "POWER") "0.0625W")
        (field (name "AUTHOR") "CERN DEM JLC")
      )
      (libsource (lib "Resistors") (part "Resistor - 1%"))
    )
    (comp (ref "R81")
      (value "33k")
      (footprint "RESC1005X40N")
      (description "Resistor - 1%")
      (fields
        (field (name "TOLERANCE") "±1%")
        (field (name "PART NUMBER") "R0402_33K_1%_0.0625W_100PPM")
        (field (name "POWER") "0.0625W")
        (field (name "AUTHOR") "CERN DEM JLC")
      )
      (libsource (lib "Resistors") (part "Resistor - 1%"))
    )
    (comp (ref "R82")
      (value "3k")
      (footprint "RESC1005X40N")
      (description "Resistor - 1%")
      (fields
        (field (name "TOLERANCE") "±1%")
        (field (name "PART NUMBER") "R0402_3K_1%_0.0625W_100PPM")
        (field (name "POWER") "0.0625W")
        (field (name "AUTHOR") "CERN DEM JLC")
      )
      (libsource (lib "Resistors") (part "Resistor - 1%"))
    )
    (comp (ref "R83")
      (value "3k")
      (footprint "RESC1005X40N")
      (description "Resistor - 1%")
      (fields
        (field (name "TOLERANCE") "±1%")
        (field (name "PART NUMBER") "R0402_3K_1%_0.0625W_100PPM")
        (field (name "POWER") "0.0625W")
        (field (name "AUTHOR") "CERN DEM JLC")
      )
      (libsource (lib "Resistors") (part "Resistor - 1%"))
    )
    (comp (ref "R84")
      (value "499")
      (footprint "RESC1005X40N")
      (description "Resistor - 1%")
      (fields
        (field (name "TOLERANCE") "±1%")
        (field (name "PART NUMBER") "R0402_499R_1%_0.1W_100PPM")
        (field (name "POWER") "0.1W")
        (field (name "AUTHOR") "CERN DEM MR")
      )
      (libsource (lib "Resistors") (part "Resistor - 1%"))
    )
    (comp (ref "R85")
      (value "33k")
      (footprint "RESC1005X40N")
      (description "Resistor - 1%")
      (fields
        (field (name "TOLERANCE") "±1%")
        (field (name "PART NUMBER") "R0402_33K_1%_0.0625W_100PPM")
        (field (name "POWER") "0.0625W")
        (field (name "AUTHOR") "CERN DEM JLC")
      )
      (libsource (lib "Resistors") (part "Resistor - 1%"))
    )
    (comp (ref "R86")
      (value "11k")
      (footprint "RESC1005X40N")
      (description "Resistor - 1%")
      (fields
        (field (name "TOLERANCE") "±1%")
        (field (name "PART NUMBER") "R0402_11K_1%_0.0625W_100PPM")
        (field (name "POWER") "0.0625W")
        (field (name "AUTHOR") "CERN DEM JLC")
      )
      (libsource (lib "Resistors") (part "Resistor - 1%"))
    )
    (comp (ref "R87")
      (value "3k")
      (footprint "RESC1005X40N")
      (description "Resistor - 1%")
      (fields
        (field (name "TOLERANCE") "±1%")
        (field (name "PART NUMBER") "R0402_3K_1%_0.0625W_100PPM")
        (field (name "POWER") "0.0625W")
        (field (name "AUTHOR") "CERN DEM JLC")
      )
      (libsource (lib "Resistors") (part "Resistor - 1%"))
    )
    (comp (ref "R88")
      (value "3k")
      (footprint "RESC1005X40N")
      (description "Resistor - 1%")
      (fields
        (field (name "TOLERANCE") "±1%")
        (field (name "PART NUMBER") "R0402_3K_1%_0.0625W_100PPM")
        (field (name "POWER") "0.0625W")
        (field (name "AUTHOR") "CERN DEM JLC")
      )
      (libsource (lib "Resistors") (part "Resistor - 1%"))
    )
    (comp (ref "R89")
      (value "11k")
      (footprint "RESC1005X40N")
      (description "Resistor - 1%")
      (fields
        (field (name "TOLERANCE") "±1%")
        (field (name "PART NUMBER") "R0402_11K_1%_0.0625W_100PPM")
        (field (name "POWER") "0.0625W")
        (field (name "AUTHOR") "CERN DEM JLC")
      )
      (libsource (lib "Resistors") (part "Resistor - 1%"))
    )
    (comp (ref "R90")
      (value "33k")
      (footprint "RESC1005X40N")
      (description "Resistor - 1%")
      (fields
        (field (name "TOLERANCE") "±1%")
        (field (name "PART NUMBER") "R0402_33K_1%_0.0625W_100PPM")
        (field (name "POWER") "0.0625W")
        (field (name "AUTHOR") "CERN DEM JLC")
      )
      (libsource (lib "Resistors") (part "Resistor - 1%"))
    )
    (comp (ref "R91")
      (value "11k")
      (footprint "RESC1005X40N")
      (description "Resistor - 1%")
      (fields
        (field (name "TOLERANCE") "±1%")
        (field (name "PART NUMBER") "R0402_11K_1%_0.0625W_100PPM")
        (field (name "POWER") "0.0625W")
        (field (name "AUTHOR") "CERN DEM JLC")
      )
      (libsource (lib "Resistors") (part "Resistor - 1%"))
    )
    (comp (ref "R92")
      (value "33k")
      (footprint "RESC1005X40N")
      (description "Resistor - 1%")
      (fields
        (field (name "TOLERANCE") "±1%")
        (field (name "PART NUMBER") "R0402_33K_1%_0.0625W_100PPM")
        (field (name "POWER") "0.0625W")
        (field (name "AUTHOR") "CERN DEM JLC")
      )
      (libsource (lib "Resistors") (part "Resistor - 1%"))
    )
    (comp (ref "R93")
      (value "3k")
      (footprint "RESC1005X40N")
      (description "Resistor - 1%")
      (fields
        (field (name "TOLERANCE") "±1%")
        (field (name "PART NUMBER") "R0402_3K_1%_0.0625W_100PPM")
        (field (name "POWER") "0.0625W")
        (field (name "AUTHOR") "CERN DEM JLC")
      )
      (libsource (lib "Resistors") (part "Resistor - 1%"))
    )
    (comp (ref "R94")
      (value "3k")
      (footprint "RESC1005X40N")
      (description "Resistor - 1%")
      (fields
        (field (name "TOLERANCE") "±1%")
        (field (name "PART NUMBER") "R0402_3K_1%_0.0625W_100PPM")
        (field (name "POWER") "0.0625W")
        (field (name "AUTHOR") "CERN DEM JLC")
      )
      (libsource (lib "Resistors") (part "Resistor - 1%"))
    )
    (comp (ref "R95")
      (value "33k")
      (footprint "RESC1005X40N")
      (description "Resistor - 1%")
      (fields
        (field (name "TOLERANCE") "±1%")
        (field (name "PART NUMBER") "R0402_33K_1%_0.0625W_100PPM")
        (field (name "POWER") "0.0625W")
        (field (name "AUTHOR") "CERN DEM JLC")
      )
      (libsource (lib "Resistors") (part "Resistor - 1%"))
    )
    (comp (ref "R96")
      (value "11k")
      (footprint "RESC1005X40N")
      (description "Resistor - 1%")
      (fields
        (field (name "TOLERANCE") "±1%")
        (field (name "PART NUMBER") "R0402_11K_1%_0.0625W_100PPM")
        (field (name "POWER") "0.0625W")
        (field (name "AUTHOR") "CERN DEM JLC")
      )
      (libsource (lib "Resistors") (part "Resistor - 1%"))
    )
    (comp (ref "R97")
      (value "3k")
      (footprint "RESC1005X40N")
      (description "Resistor - 1%")
      (fields
        (field (name "TOLERANCE") "±1%")
        (field (name "PART NUMBER") "R0402_3K_1%_0.0625W_100PPM")
        (field (name "POWER") "0.0625W")
        (field (name "AUTHOR") "CERN DEM JLC")
      )
      (libsource (lib "Resistors") (part "Resistor - 1%"))
    )
    (comp (ref "R98")
      (value "3k")
      (footprint "RESC1005X40N")
      (description "Resistor - 1%")
      (fields
        (field (name "TOLERANCE") "±1%")
        (field (name "PART NUMBER") "R0402_3K_1%_0.0625W_100PPM")
        (field (name "POWER") "0.0625W")
        (field (name "AUTHOR") "CERN DEM JLC")
      )
      (libsource (lib "Resistors") (part "Resistor - 1%"))
    )
    (comp (ref "R99")
      (value "499")
      (footprint "RESC1005X40N")
      (description "Resistor - 1%")
      (fields
        (field (name "TOLERANCE") "±1%")
        (field (name "PART NUMBER") "R0402_499R_1%_0.1W_100PPM")
        (field (name "POWER") "0.1W")
        (field (name "AUTHOR") "CERN DEM MR")
      )
      (libsource (lib "Resistors") (part "Resistor - 1%"))
    )
    (comp (ref "R125")
      (value "499")
      (footprint "RESC1005X40N")
      (description "Resistor - 1%")
      (fields
        (field (name "TOLERANCE") "±1%")
        (field (name "PART NUMBER") "R0402_499R_1%_0.1W_100PPM")
        (field (name "POWER") "0.1W")
        (field (name "AUTHOR") "CERN DEM MR")
      )
      (libsource (lib "Resistors") (part "Resistor - 1%"))
    )
    (comp (ref "R126")
      (value "499")
      (footprint "RESC1005X40N")
      (description "Resistor - 1%")
      (fields
        (field (name "TOLERANCE") "±1%")
        (field (name "PART NUMBER") "R0402_499R_1%_0.1W_100PPM")
        (field (name "POWER") "0.1W")
        (field (name "AUTHOR") "CERN DEM MR")
      )
      (libsource (lib "Resistors") (part "Resistor - 1%"))
    )
    (comp (ref "R127")
      (value "499")
      (footprint "RESC1005X40N")
      (description "Resistor - 1%")
      (fields
        (field (name "TOLERANCE") "±1%")
        (field (name "PART NUMBER") "R0402_499R_1%_0.1W_100PPM")
        (field (name "POWER") "0.1W")
        (field (name "AUTHOR") "CERN DEM MR")
      )
      (libsource (lib "Resistors") (part "Resistor - 1%"))
    )
    (comp (ref "R128")
      (value "499")
      (footprint "RESC1005X40N")
      (description "Resistor - 1%")
      (fields
        (field (name "TOLERANCE") "±1%")
        (field (name "PART NUMBER") "R0402_499R_1%_0.1W_100PPM")
        (field (name "POWER") "0.1W")
        (field (name "AUTHOR") "CERN DEM MR")
      )
      (libsource (lib "Resistors") (part "Resistor - 1%"))
    )
    (comp (ref "R129")
      (value "499")
      (footprint "RESC1005X40N")
      (description "Resistor - 1%")
      (fields
        (field (name "TOLERANCE") "±1%")
        (field (name "PART NUMBER") "R0402_499R_1%_0.1W_100PPM")
        (field (name "POWER") "0.1W")
        (field (name "AUTHOR") "CERN DEM MR")
      )
      (libsource (lib "Resistors") (part "Resistor - 1%"))
    )
    (comp (ref "R130")
      (value "499")
      (footprint "RESC1005X40N")
      (description "Resistor - 1%")
      (fields
        (field (name "TOLERANCE") "±1%")
        (field (name "PART NUMBER") "R0402_499R_1%_0.1W_100PPM")
        (field (name "POWER") "0.1W")
        (field (name "AUTHOR") "CERN DEM MR")
      )
      (libsource (lib "Resistors") (part "Resistor - 1%"))
    )
    (comp (ref "R131")
      (value "499")
      (footprint "RESC1005X40N")
      (description "Resistor - 1%")
      (fields
        (field (name "TOLERANCE") "±1%")
        (field (name "PART NUMBER") "R0402_499R_1%_0.1W_100PPM")
        (field (name "POWER") "0.1W")
        (field (name "AUTHOR") "CERN DEM MR")
      )
      (libsource (lib "Resistors") (part "Resistor - 1%"))
    )
    (comp (ref "T5")
      (value "BSS138LT1G")
      (footprint "SOT95P240X110-3N")
      (description "N-CHANNEL MOSFET WITH DIODE")
      (fields (field (name "MANUFACTURER") "ON SEMICONDUCTOR") (field (name "AUTHOR") "CERN DEM JLC"))
      (libsource (lib "ICs And Semiconductors") (part "N-MOSFET-D 1G 2S 3D"))
    )
    (comp (ref "T6")
      (value "BSS138LT1G")
      (footprint "SOT95P240X110-3N")
      (description "N-CHANNEL MOSFET WITH DIODE")
      (fields (field (name "MANUFACTURER") "ON SEMICONDUCTOR") (field (name "AUTHOR") "CERN DEM JLC"))
      (libsource (lib "ICs And Semiconductors") (part "N-MOSFET-D 1G 2S 3D"))
    )
    (comp (ref "T8")
      (value "BSS138LT1G")
      (footprint "SOT95P240X110-3N")
      (description "N-CHANNEL MOSFET WITH DIODE")
      (fields (field (name "MANUFACTURER") "ON SEMICONDUCTOR") (field (name "AUTHOR") "CERN DEM JLC"))
      (libsource (lib "ICs And Semiconductors") (part "N-MOSFET-D 1G 2S 3D"))
    )
    (comp (ref "T9")
      (value "BSS138LT1G")
      (footprint "SOT95P240X110-3N")
      (description "N-CHANNEL MOSFET WITH DIODE")
      (fields (field (name "MANUFACTURER") "ON SEMICONDUCTOR") (field (name "AUTHOR") "CERN DEM JLC"))
      (libsource (lib "ICs And Semiconductors") (part "N-MOSFET-D 1G 2S 3D"))
    )
    (comp (ref "T10")
      (value "BSS138LT1G")
      (footprint "SOT95P240X110-3N")
      (description "N-CHANNEL MOSFET WITH DIODE")
      (fields (field (name "MANUFACTURER") "ON SEMICONDUCTOR") (field (name "AUTHOR") "CERN DEM JLC"))
      (libsource (lib "ICs And Semiconductors") (part "N-MOSFET-D 1G 2S 3D"))
    )
    (comp (ref "T11")
      (value "BSS138LT1G")
      (footprint "SOT95P240X110-3N")
      (description "N-CHANNEL MOSFET WITH DIODE")
      (fields (field (name "MANUFACTURER") "ON SEMICONDUCTOR") (field (name "AUTHOR") "CERN DEM JLC"))
      (libsource (lib "ICs And Semiconductors") (part "N-MOSFET-D 1G 2S 3D"))
    )
    (comp (ref "T12")
      (value "BSS138LT1G")
      (footprint "SOT95P240X110-3N")
      (description "N-CHANNEL MOSFET WITH DIODE")
      (fields (field (name "MANUFACTURER") "ON SEMICONDUCTOR") (field (name "AUTHOR") "CERN DEM JLC"))
      (libsource (lib "ICs And Semiconductors") (part "N-MOSFET-D 1G 2S 3D"))
    )
    (comp (ref "T13")
      (value "BSS138LT1G")
      (footprint "SOT95P240X110-3N")
      (description "N-CHANNEL MOSFET WITH DIODE")
      (fields (field (name "MANUFACTURER") "ON SEMICONDUCTOR") (field (name "AUTHOR") "CERN DEM JLC"))
      (libsource (lib "ICs And Semiconductors") (part "N-MOSFET-D 1G 2S 3D"))
    )
    (comp (ref "T14")
      (value "BSS138LT1G")
      (footprint "SOT95P240X110-3N")
      (description "N-CHANNEL MOSFET WITH DIODE")
      (fields (field (name "MANUFACTURER") "ON SEMICONDUCTOR") (field (name "AUTHOR") "CERN DEM JLC"))
      (libsource (lib "ICs And Semiconductors") (part "N-MOSFET-D 1G 2S 3D"))
    )
  )
  (nets
    (net (code "1") (name "/AFE_EN") (class "Default")
      (node (ref "C111") (pin "2") (pinfunction "2_2") (pintype "passive"))
      (node (ref "IC17") (pin "4") (pinfunction "EN/UV_4") (pintype "input"))
      (node (ref "IC20") (pin "3") (pinfunction "EN/UV_3") (pintype "input"))
      (node (ref "IC27") (pin "1") (pinfunction "~{SHDN}_1") (pintype "input"))
      (node (ref "R77") (pin "1") (pinfunction "1_1") (pintype "passive"))
      (node (ref "T6") (pin "3") (pinfunction "D_3") (pintype "passive"))
    )
    (net (code "2") (name "/AP62201_BST") (class "Default")
      (node (ref "C101") (pin "1") (pinfunction "1_1") (pintype "passive"))
      (node (ref "IC23") (pin "6") (pinfunction "BST_6") (pintype "input"))
    )
    (net (code "3") (name "/AP62201_FB") (class "Default")
      (node (ref "IC23") (pin "4") (pinfunction "FB_4") (pintype "input"))
      (node (ref "R74") (pin "1") (pinfunction "1_1") (pintype "passive"))
      (node (ref "R75") (pin "2") (pinfunction "2_2") (pintype "passive"))
    )
    (net (code "4") (name "/AP62201_SW") (class "Default")
      (node (ref "C101") (pin "2") (pinfunction "2_2") (pintype "passive"))
      (node (ref "IC23") (pin "2") (pinfunction "SW_2") (pintype "output"))
      (node (ref "L14") (pin "1") (pinfunction "1_1") (pintype "passive"))
    )
    (net (code "5") (name "/CH_EN") (class "Default")
      (node (ref "IC19") (pin "4") (pinfunction "EN/UV_4") (pintype "input"))
      (node (ref "IC21") (pin "2") (pinfunction "EN/UV_2") (pintype "input"))
      (node (ref "IC29") (pin "4") (pinfunction "EN/UV_4") (pintype "input"))
    )
    (net (code "6") (name "/LT3045_P5V0") (class "Default")
      (node (ref "C84") (pin "2") (pinfunction "2_2") (pintype "passive"))
      (node (ref "C85") (pin "2") (pinfunction "2_2") (pintype "passive"))
      (node (ref "IC19") (pin "10") (pinfunction "OUTS_10") (pintype "input"))
      (node (ref "IC19") (pin "11") (pinfunction "OUT_11") (pintype "power_in"))
      (node (ref "IC19") (pin "12") (pinfunction "OUT_12") (pintype "power_in"))
      (node (ref "L8") (pin "1") (pinfunction "1_1") (pintype "passive"))
    )
    (net (code "7") (name "/N5V0_PG") (class "Default")
      (node (ref "IC21") (pin "4") (pinfunction "PG_4") (pintype "output"))
      (node (ref "IC24") (pin "2") (pinfunction "B_2") (pintype "input"))
      (node (ref "R72") (pin "1") (pinfunction "1_1") (pintype "passive"))
      (node (ref "T12") (pin "1") (pinfunction "G_1") (pintype "passive"))
    )
    (net (code "8") (name "/N5V6") (class "Default")
      (node (ref "C93") (pin "1") (pinfunction "1_1") (pintype "passive"))
      (node (ref "C94") (pin "1") (pinfunction "1_1") (pintype "passive"))
      (node (ref "C95") (pin "1") (pinfunction "1_1") (pintype "passive"))
      (node (ref "C96") (pin "1") (pinfunction "1_1") (pintype "passive"))
      (node (ref "C98") (pin "2") (pinfunction "2_2") (pintype "passive"))
      (node (ref "IC21") (pin "12") (pinfunction "GND_12") (pintype "power_in"))
      (node (ref "IC21") (pin "13") (pinfunction "PAD_13") (pintype "power_in"))
      (node (ref "IC22") (pin "2") (pinfunction "VIN_2") (pintype "input"))
      (node (ref "IC22") (pin "3") (pinfunction "EN_3") (pintype "input"))
      (node (ref "R69") (pin "1") (pinfunction "1_1") (pintype "passive"))
      (node (ref "R70") (pin "1") (pinfunction "1_1") (pintype "passive"))
    )
    (net (code "9") (name "/N14V7_LNA_ILIM") (class "Default")
      (node (ref "IC20") (pin "6") (pinfunction "ILIM_6") (pintype "input"))
      (node (ref "R67") (pin "2") (pinfunction "2_2") (pintype "passive"))
    )
    (net (code "10") (name "/N14V7_LNA_PG") (class "Default")
      (node (ref "IC20") (pin "4") (pinfunction "PG_4") (pintype "output"))
      (node (ref "T14") (pin "1") (pinfunction "G_1") (pintype "passive"))
    )
    (net (code "11") (name "/N14V7_LNA_SET") (class "Default")
      (node (ref "C92") (pin "2") (pinfunction "2_2") (pintype "passive"))
      (node (ref "IC20") (pin "8") (pinfunction "SET_8") (pintype "input"))
      (node (ref "R68") (pin "2") (pinfunction "2_2") (pintype "passive"))
    )
    (net (code "12") (name "/N15V0") (class "Default")
      (node (ref "C74") (pin "2") (pinfunction "2_2") (pintype "passive"))
      (node (ref "C81") (pin "1") (pinfunction "1_1") (pintype "passive"))
      (node (ref "C88") (pin "2") (pinfunction "2_2") (pintype "passive"))
      (node (ref "IC20") (pin "1") (pinfunction "IN_1") (pintype "input"))
      (node (ref "IC20") (pin "13") (pinfunction "IN_13") (pintype "input"))
      (node (ref "IC20") (pin "2") (pinfunction "IN_2") (pintype "input"))
      (node (ref "IC20") (pin "5") (pinfunction "PGFB_5") (pintype "input"))
      (node (ref "L11") (pin "2") (pinfunction "2_2") (pintype "passive"))
    )
    (net (code "13") (name "/P1V1 EN") (class "Default")
      (node (ref "IC24") (pin "4") (pinfunction "Y_4") (pintype "output"))
      (node (ref "IC26") (pin "4") (pinfunction "EN/UV_4") (pintype "input"))
      (node (ref "IC28") (pin "4") (pinfunction "EN/UV_4") (pintype "input"))
    )
    (net (code "14") (name "/P1V1_IO_ILIM") (class "Default")
      (node (ref "IC28") (pin "6") (pinfunction "ILIM_6") (pintype "input"))
      (node (ref "R93") (pin "2") (pinfunction "2_2") (pintype "passive"))
    )
    (net (code "15") (name "/P1V1_IO_PGFB") (class "Default")
      (node (ref "IC28") (pin "7") (pinfunction "PGFB_7") (pintype "input"))
      (node (ref "R90") (pin "1") (pinfunction "1_1") (pintype "passive"))
      (node (ref "R94") (pin "2") (pinfunction "2_2") (pintype "passive"))
    )
    (net (code "16") (name "/P1V1_IO_SET") (class "Default")
      (node (ref "C128") (pin "2") (pinfunction "2_2") (pintype "passive"))
      (node (ref "IC28") (pin "8") (pinfunction "SET_8") (pintype "input"))
      (node (ref "R91") (pin "2") (pinfunction "2_2") (pintype "passive"))
    )
    (net (code "17") (name "/P1V1_PG") (class "Default")
      (node (ref "IC25") (pin "4") (pinfunction "EN/UV_4") (pintype "input"))
      (node (ref "IC26") (pin "5") (pinfunction "PG_5") (pintype "output"))
      (node (ref "IC28") (pin "5") (pinfunction "PG_5") (pintype "output"))
      (node (ref "R79") (pin "1") (pinfunction "1_1") (pintype "passive"))
      (node (ref "T8") (pin "1") (pinfunction "G_1") (pintype "passive"))
    )
    (net (code "18") (name "/P1V1_VDD_ILIM") (class "Default")
      (node (ref "IC26") (pin "6") (pinfunction "ILIM_6") (pintype "input"))
      (node (ref "R87") (pin "2") (pinfunction "2_2") (pintype "passive"))
    )
    (net (code "19") (name "/P1V1_VDD_PGFB") (class "Default")
      (node (ref "IC26") (pin "7") (pinfunction "PGFB_7") (pintype "input"))
      (node (ref "R85") (pin "1") (pinfunction "1_1") (pintype "passive"))
      (node (ref "R88") (pin "2") (pinfunction "2_2") (pintype "passive"))
    )
    (net (code "20") (name "/P1V1_VDD_SET") (class "Default")
      (node (ref "C115") (pin "2") (pinfunction "2_2") (pintype "passive"))
      (node (ref "IC26") (pin "8") (pinfunction "SET_8") (pintype "input"))
      (node (ref "R86") (pin "2") (pinfunction "2_2") (pintype "passive"))
    )
    (net (code "21") (name "/P3V3_ADC_ILIM") (class "Default")
      (node (ref "IC25") (pin "6") (pinfunction "ILIM_6") (pintype "input"))
      (node (ref "R82") (pin "2") (pinfunction "2_2") (pintype "passive"))
    )
    (net (code "22") (name "/P3V3_ADC_PG") (class "Default")
      (node (ref "IC25") (pin "5") (pinfunction "PG_5") (pintype "output"))
      (node (ref "R80") (pin "1") (pinfunction "1_1") (pintype "passive"))
      (node (ref "T5") (pin "1") (pinfunction "G_1") (pintype "passive"))
      (node (ref "T9") (pin "1") (pinfunction "G_1") (pintype "passive"))
    )
    (net (code "23") (name "/P3V3_ADC_PGFB") (class "Default")
      (node (ref "IC25") (pin "7") (pinfunction "PGFB_7") (pintype "input"))
      (node (ref "R78") (pin "1") (pinfunction "1_1") (pintype "passive"))
      (node (ref "R83") (pin "2") (pinfunction "2_2") (pintype "passive"))
    )
    (net (code "24") (name "/P3V3_ADC_SET") (class "Default")
      (node (ref "C112") (pin "2") (pinfunction "2_2") (pintype "passive"))
      (node (ref "IC25") (pin "8") (pinfunction "SET_8") (pintype "input"))
      (node (ref "R81") (pin "2") (pinfunction "2_2") (pintype "passive"))
    )
    (net (code "25") (name "/P3V3_CLK_ILIM") (class "Default")
      (node (ref "IC29") (pin "6") (pinfunction "ILIM_6") (pintype "input"))
      (node (ref "R97") (pin "2") (pinfunction "2_2") (pintype "passive"))
    )
    (net (code "26") (name "/P3V3_CLK_PG") (class "Default")
      (node (ref "IC29") (pin "5") (pinfunction "PG_5") (pintype "output"))
      (node (ref "T10") (pin "1") (pinfunction "G_1") (pintype "passive"))
    )
    (net (code "27") (name "/P3V3_CLK_PGFB") (class "Default")
      (node (ref "IC29") (pin "7") (pinfunction "PGFB_7") (pintype "input"))
      (node (ref "R92") (pin "1") (pinfunction "1_1") (pintype "passive"))
      (node (ref "R98") (pin "2") (pinfunction "2_2") (pintype "passive"))
    )
    (net (code "28") (name "/P3V3_CLK_SET") (class "Default")
      (node (ref "C129") (pin "2") (pinfunction "2_2") (pintype "passive"))
      (node (ref "IC29") (pin "8") (pinfunction "SET_8") (pintype "input"))
      (node (ref "R95") (pin "2") (pinfunction "2_2") (pintype "passive"))
    )
    (net (code "29") (name "/P5V0_ILIM") (class "Default")
      (node (ref "IC19") (pin "6") (pinfunction "ILIM_6") (pintype "input"))
      (node (ref "R64") (pin "2") (pinfunction "2_2") (pintype "passive"))
    )
    (net (code "30") (name "/P5V0_PG") (class "Default")
      (node (ref "IC19") (pin "5") (pinfunction "PG_5") (pintype "output"))
      (node (ref "IC24") (pin "1") (pinfunction "A_1") (pintype "input"))
      (node (ref "R71") (pin "1") (pinfunction "1_1") (pintype "passive"))
      (node (ref "T11") (pin "1") (pinfunction "G_1") (pintype "passive"))
    )
    (net (code "31") (name "/P5V0_PGFB") (class "Default")
      (node (ref "IC19") (pin "7") (pinfunction "PGFB_7") (pintype "input"))
      (node (ref "R61") (pin "1") (pinfunction "1_1") (pintype "passive"))
      (node (ref "R65") (pin "2") (pinfunction "2_2") (pintype "passive"))
    )
    (net (code "32") (name "/P5V0_SET") (class "Default")
      (node (ref "C87") (pin "2") (pinfunction "2_2") (pintype "passive"))
      (node (ref "IC19") (pin "8") (pinfunction "SET_8") (pintype "input"))
      (node (ref "R62") (pin "2") (pinfunction "2_2") (pintype "passive"))
      (node (ref "R63") (pin "2") (pinfunction "2_2") (pintype "passive"))
    )
    (net (code "33") (name "/P14V7_LNA_ILIM") (class "Default")
      (node (ref "IC17") (pin "6") (pinfunction "ILIM_6") (pintype "input"))
      (node (ref "R60") (pin "2") (pinfunction "2_2") (pintype "passive"))
    )
    (net (code "34") (name "/P14V7_LNA_PG") (class "Default")
      (node (ref "IC17") (pin "5") (pinfunction "PG_5") (pintype "output"))
      (node (ref "T13") (pin "1") (pinfunction "G_1") (pintype "passive"))
    )
    (net (code "35") (name "/P14V7_LNA_SET") (class "Default")
      (node (ref "C82") (pin "2") (pinfunction "2_2") (pintype "passive"))
      (node (ref "IC17") (pin "8") (pinfunction "SET_8") (pintype "input"))
      (node (ref "R59") (pin "2") (pinfunction "2_2") (pintype "passive"))
    )
    (net (code "36") (name "/P15V0") (class "Default")
      (node (ref "C56") (pin "2") (pinfunction "2_2") (pintype "passive"))
      (node (ref "C58") (pin "1") (pinfunction "1_1") (pintype "passive"))
      (node (ref "C62") (pin "2") (pinfunction "2_2") (pintype "passive"))
      (node (ref "IC17") (pin "1") (pinfunction "IN_1") (pintype "input"))
      (node (ref "IC17") (pin "2") (pinfunction "IN_2") (pintype "input"))
      (node (ref "IC17") (pin "3") (pinfunction "IN_3") (pintype "input"))
      (node (ref "IC17") (pin "7") (pinfunction "PGFB_7") (pintype "input"))
      (node (ref "L6") (pin "2") (pinfunction "2_2") (pintype "passive"))
    )
    (net (code "37") (name "GND") (class "Default")
      (node (ref "C100") (pin "1") (pinfunction "1_1") (pintype "passive"))
      (node (ref "C102") (pin "1") (pinfunction "1_1") (pintype "passive"))
      (node (ref "C103") (pin "1") (pinfunction "1_1") (pintype "passive"))
      (node (ref "C104") (pin "1") (pinfunction "1_1") (pintype "passive"))
      (node (ref "C105") (pin "1") (pinfunction "1_1") (pintype "passive"))
      (node (ref "C106") (pin "1") (pinfunction "1_1") (pintype "passive"))
      (node (ref "C107") (pin "1") (pinfunction "1_1") (pintype "passive"))
      (node (ref "C108") (pin "1") (pinfunction "1_1") (pintype "passive"))
      (node (ref "C109") (pin "1") (pinfunction "1_1") (pintype "passive"))
      (node (ref "C110") (pin "1") (pinfunction "1_1") (pintype "passive"))
      (node (ref "C111") (pin "1") (pinfunction "1_1") (pintype "passive"))
      (node (ref "C112") (pin "1") (pinfunction "1_1") (pintype "passive"))
      (node (ref "C113") (pin "1") (pinfunction "1_1") (pintype "passive"))
      (node (ref "C114") (pin "1") (pinfunction "1_1") (pintype "passive"))
      (node (ref "C115") (pin "1") (pinfunction "1_1") (pintype "passive"))
      (node (ref "C116") (pin "1") (pinfunction "1_1") (pintype "passive"))
      (node (ref "C117") (pin "1") (pinfunction "1_1") (pintype "passive"))
      (node (ref "C118") (pin "1") (pinfunction "1_1") (pintype "passive"))
      (node (ref "C119") (pin "2") (pinfunction "2_2") (pintype "passive"))
      (node (ref "C120") (pin "1") (pinfunction "1_1") (pintype "passive"))
      (node (ref "C121") (pin "1") (pinfunction "1_1") (pintype "passive"))
      (node (ref "C122") (pin "1") (pinfunction "1_1") (pintype "passive"))
      (node (ref "C123") (pin "1") (pinfunction "1_1") (pintype "passive"))
      (node (ref "C124") (pin "1") (pinfunction "1_1") (pintype "passive"))
      (node (ref "C125") (pin "1") (pinfunction "1_1") (pintype "passive"))
      (node (ref "C126") (pin "1") (pinfunction "1_1") (pintype "passive"))
      (node (ref "C127") (pin "1") (pinfunction "1_1") (pintype "passive"))
      (node (ref "C128") (pin "1") (pinfunction "1_1") (pintype "passive"))
      (node (ref "C129") (pin "1") (pinfunction "1_1") (pintype "passive"))
      (node (ref "C56") (pin "1") (pinfunction "1_1") (pintype "passive"))
      (node (ref "C57") (pin "2") (pinfunction "2_2") (pintype "passive"))
      (node (ref "C58") (pin "2") (pinfunction "2_2") (pintype "passive"))
      (node (ref "C59") (pin "1") (pinfunction "1_1") (pintype "passive"))
      (node (ref "C60") (pin "1") (pinfunction "1_1") (pintype "passive"))
      (node (ref "C61") (pin "1") (pinfunction "1_1") (pintype "passive"))
      (node (ref "C62") (pin "1") (pinfunction "1_1") (pintype "passive"))
      (node (ref "C63") (pin "2") (pinfunction "2_2") (pintype "passive"))
      (node (ref "C64") (pin "1") (pinfunction "1_1") (pintype "passive"))
      (node (ref "C65") (pin "1") (pinfunction "1_1") (pintype "passive"))
      (node (ref "C66") (pin "1") (pinfunction "1_1") (pintype "passive"))
      (node (ref "C67") (pin "1") (pinfunction "1_1") (pintype "passive"))
      (node (ref "C68") (pin "1") (pinfunction "1_1") (pintype "passive"))
      (node (ref "C69") (pin "1") (pinfunction "1_1") (pintype "passive"))
      (node (ref "C70") (pin "1") (pinfunction "1_1") (pintype "passive"))
      (node (ref "C71") (pin "1") (pinfunction "1_1") (pintype "passive"))
      (node (ref "C72") (pin "1") (pinfunction "1_1") (pintype "passive"))
      (node (ref "C73") (pin "1") (pinfunction "1_1") (pintype "passive"))
      (node (ref "C74") (pin "1") (pinfunction "1_1") (pintype "passive"))
      (node (ref "C75") (pin "1") (pinfunction "1_1") (pintype "passive"))
      (node (ref "C76") (pin "1") (pinfunction "1_1") (pintype "passive"))
      (node (ref "C77") (pin "1") (pinfunction "1_1") (pintype "passive"))
      (node (ref "C78") (pin "2") (pinfunction "2_2") (pintype "passive"))
      (node (ref "C79") (pin "2") (pinfunction "2_2") (pintype "passive"))
      (node (ref "C80") (pin "2") (pinfunction "2_2") (pintype "passive"))
      (node (ref "C81") (pin "2") (pinfunction "2_2") (pintype "passive"))
      (node (ref "C82") (pin "1") (pinfunction "1_1") (pintype "passive"))
      (node (ref "C83") (pin "2") (pinfunction "2_2") (pintype "passive"))
      (node (ref "C84") (pin "1") (pinfunction "1_1") (pintype "passive"))
      (node (ref "C85") (pin "1") (pinfunction "1_1") (pintype "passive"))
      (node (ref "C86") (pin "1") (pinfunction "1_1") (pintype "passive"))
      (node (ref "C87") (pin "1") (pinfunction "1_1") (pintype "passive"))
      (node (ref "C88") (pin "1") (pinfunction "1_1") (pintype "passive"))
      (node (ref "C89") (pin "1") (pinfunction "1_1") (pintype "passive"))
      (node (ref "C90") (pin "1") (pinfunction "1_1") (pintype "passive"))
      (node (ref "C91") (pin "1") (pinfunction "1_1") (pintype "passive"))
      (node (ref "C92") (pin "1") (pinfunction "1_1") (pintype "passive"))
      (node (ref "C93") (pin "2") (pinfunction "2_2") (pintype "passive"))
      (node (ref "C94") (pin "2") (pinfunction "2_2") (pintype "passive"))
      (node (ref "C97") (pin "2") (pinfunction "2_2") (pintype "passive"))
      (node (ref "C98") (pin "1") (pinfunction "1_1") (pintype "passive"))
      (node (ref "C99") (pin "1") (pinfunction "1_1") (pintype "passive"))
      (node (ref "IC17") (pin "13") (pinfunction "GND_13") (pintype "power_in"))
      (node (ref "IC17") (pin "9") (pinfunction "GND_9") (pintype "power_in"))
      (node (ref "IC18") (pin "16") (pinfunction "0V_16") (pintype "power_in"))
      (node (ref "IC18") (pin "2") (pinfunction "-Vin_2") (pintype "power_in"))
      (node (ref "IC18") (pin "3") (pinfunction "-Vin_3") (pintype "power_in"))
      (node (ref "IC18") (pin "9") (pinfunction "0V_9") (pintype "power_in"))
      (node (ref "IC19") (pin "13") (pinfunction "GND_13") (pintype "power_in"))
      (node (ref "IC19") (pin "9") (pinfunction "GND_9") (pintype "power_in"))
      (node (ref "IC20") (pin "9") (pinfunction "GND_9") (pintype "power_in"))
      (node (ref "IC21") (pin "9") (pinfunction "BIAS_9") (pintype "power_in"))
      (node (ref "IC22") (pin "1") (pinfunction "GND_1") (pintype "power_in"))
      (node (ref "IC23") (pin "1") (pinfunction "GND_1") (pintype "power_in"))
      (node (ref "IC24") (pin "3") (pinfunction "GND_3") (pintype "power_in"))
      (node (ref "IC25") (pin "13") (pinfunction "GND_13") (pintype "power_in"))
      (node (ref "IC25") (pin "9") (pinfunction "GND_9") (pintype "power_in"))
      (node (ref "IC26") (pin "13") (pinfunction "GND_13") (pintype "power_in"))
      (node (ref "IC26") (pin "9") (pinfunction "GND_9") (pintype "power_in"))
      (node (ref "IC27") (pin "3") (pinfunction "GND_3") (pintype "power_in"))
      (node (ref "IC27") (pin "4") (pinfunction "GND_4") (pintype "power_in"))
      (node (ref "IC27") (pin "5") (pinfunction "GND_5") (pintype "power_in"))
      (node (ref "IC27") (pin "8") (pinfunction "GND_8") (pintype "power_in"))
      (node (ref "IC28") (pin "13") (pinfunction "GND_13") (pintype "power_in"))
      (node (ref "IC28") (pin "9") (pinfunction "GND_9") (pintype "power_in"))
      (node (ref "IC29") (pin "13") (pinfunction "GND_13") (pintype "power_in"))
      (node (ref "IC29") (pin "9") (pinfunction "GND_9") (pintype "power_in"))
      (node (ref "L12") (pin "2") (pinfunction "2_2") (pintype "passive"))
      (node (ref "R59") (pin "1") (pinfunction "1_1") (pintype "passive"))
      (node (ref "R60") (pin "1") (pinfunction "1_1") (pintype "passive"))
      (node (ref "R62") (pin "1") (pinfunction "1_1") (pintype "passive"))
      (node (ref "R63") (pin "1") (pinfunction "1_1") (pintype "passive"))
      (node (ref "R64") (pin "1") (pinfunction "1_1") (pintype "passive"))
      (node (ref "R65") (pin "1") (pinfunction "1_1") (pintype "passive"))
      (node (ref "R66") (pin "2") (pinfunction "2_2") (pintype "passive"))
      (node (ref "R67") (pin "1") (pinfunction "1_1") (pintype "passive"))
      (node (ref "R68") (pin "1") (pinfunction "1_1") (pintype "passive"))
      (node (ref "R75") (pin "1") (pinfunction "1_1") (pintype "passive"))
      (node (ref "R81") (pin "1") (pinfunction "1_1") (pintype "passive"))
      (node (ref "R82") (pin "1") (pinfunction "1_1") (pintype "passive"))
      (node (ref "R84") (pin "1") (pinfunction "1_1") (pintype "passive"))
      (node (ref "R86") (pin "1") (pinfunction "1_1") (pintype "passive"))
      (node (ref "R87") (pin "1") (pinfunction "1_1") (pintype "passive"))
      (node (ref "R89") (pin "1") (pinfunction "1_1") (pintype "passive"))
      (node (ref "R91") (pin "1") (pinfunction "1_1") (pintype "passive"))
      (node (ref "R93") (pin "1") (pinfunction "1_1") (pintype "passive"))
      (node (ref "R95") (pin "1") (pinfunction "1_1") (pintype "passive"))
      (node (ref "R96") (pin "1") (pinfunction "1_1") (pintype "passive"))
      (node (ref "R97") (pin "1") (pinfunction "1_1") (pintype "passive"))
      (node (ref "R99") (pin "1") (pinfunction "1_1") (pintype "passive"))
      (node (ref "T10") (pin "2") (pinfunction "S_2") (pintype "passive"))
      (node (ref "T11") (pin "2") (pinfunction "S_2") (pintype "passive"))
      (node (ref "T12") (pin "2") (pinfunction "S_2") (pintype "passive"))
      (node (ref "T13") (pin "2") (pinfunction "S_2") (pintype "passive"))
      (node (ref "T14") (pin "2") (pinfunction "S_2") (pintype "passive"))
      (node (ref "T5") (pin "2") (pinfunction "S_2") (pintype "passive"))
      (node (ref "T6") (pin "2") (pinfunction "S_2") (pintype "passive"))
      (node (ref "T8") (pin "2") (pinfunction "S_2") (pintype "passive"))
      (node (ref "T9") (pin "2") (pinfunction "S_2") (pintype "passive"))
    )
    (net (code "38") (name "N5V0") (class "Default")
      (node (ref "C100") (pin "2") (pinfunction "2_2") (pintype "passive"))
      (node (ref "C97") (pin "1") (pinfunction "1_1") (pintype "passive"))
      (node (ref "L13") (pin "2") (pinfunction "2_2") (pintype "passive"))
    )
    (net (code "39") (name "N14V7_LNA") (class "Default")
      (node (ref "C89") (pin "2") (pinfunction "2_2") (pintype "passive"))
      (node (ref "C90") (pin "2") (pinfunction "2_2") (pintype "passive"))
      (node (ref "IC20") (pin "10") (pinfunction "OUTS_10") (pintype "output"))
      (node (ref "IC20") (pin "11") (pinfunction "OUT_11") (pintype "power_in"))
      (node (ref "IC20") (pin "12") (pinfunction "OUT_12") (pintype "power_in"))
    )
    (net (code "40") (name "Net-(C57-Pad1)") (class "Default")
      (node (ref "C57") (pin "1") (pinfunction "1_1") (pintype "passive"))
      (node (ref "C61") (pin "2") (pinfunction "2_2") (pintype "passive"))
      (node (ref "L5") (pin "2") (pinfunction "2_2") (pintype "passive"))
      (node (ref "L6") (pin "1") (pinfunction "1_1") (pintype "passive"))
    )
    (net (code "41") (name "Net-(C60-Pad2)") (class "Default")
      (node (ref "C60") (pin "2") (pinfunction "2_2") (pintype "passive"))
      (node (ref "L4") (pin "2") (pinfunction "2_2") (pintype "passive"))
      (node (ref "L5") (pin "1") (pinfunction "1_1") (pintype "passive"))
    )
    (net (code "42") (name "Net-(C63-Pad1)") (class "Default")
      (node (ref "C63") (pin "1") (pinfunction "1_1") (pintype "passive"))
      (node (ref "C67") (pin "2") (pinfunction "2_2") (pintype "passive"))
      (node (ref "C68") (pin "2") (pinfunction "2_2") (pintype "passive"))
      (node (ref "C69") (pin "2") (pinfunction "2_2") (pintype "passive"))
      (node (ref "C70") (pin "2") (pinfunction "2_2") (pintype "passive"))
      (node (ref "C71") (pin "2") (pinfunction "2_2") (pintype "passive"))
      (node (ref "C72") (pin "2") (pinfunction "2_2") (pintype "passive"))
      (node (ref "IC18") (pin "22") (pinfunction "+Vin_22") (pintype "power_in"))
      (node (ref "IC18") (pin "23") (pinfunction "+Vin_23") (pintype "power_in"))
      (node (ref "L7") (pin "2") (pinfunction "2_2") (pintype "passive"))
    )
    (net (code "43") (name "Net-(C73-Pad2)") (class "Default")
      (node (ref "C73") (pin "2") (pinfunction "2_2") (pintype "passive"))
      (node (ref "C80") (pin "1") (pinfunction "1_1") (pintype "passive"))
      (node (ref "L10") (pin "2") (pinfunction "2_2") (pintype "passive"))
      (node (ref "L11") (pin "1") (pinfunction "1_1") (pintype "passive"))
    )
    (net (code "44") (name "Net-(C79-Pad1)") (class "Default")
      (node (ref "C79") (pin "1") (pinfunction "1_1") (pintype "passive"))
      (node (ref "L10") (pin "1") (pinfunction "1_1") (pintype "passive"))
      (node (ref "L9") (pin "2") (pinfunction "2_2") (pintype "passive"))
    )
    (net (code "45") (name "Net-(C119-Pad1)") (class "Default")
      (node (ref "C119") (pin "1") (pinfunction "1_1") (pintype "passive"))
      (node (ref "C123") (pin "2") (pinfunction "2_2") (pintype "passive"))
      (node (ref "L15") (pin "1") (pinfunction "1_1") (pintype "passive"))
      (node (ref "L16") (pin "2") (pinfunction "2_2") (pintype "passive"))
    )
    (net (code "46") (name "Net-(C124-Pad2)") (class "Default")
      (node (ref "C124") (pin "2") (pinfunction "2_2") (pintype "passive"))
      (node (ref "C125") (pin "2") (pinfunction "2_2") (pintype "passive"))
      (node (ref "IC29") (pin "1") (pinfunction "IN_1") (pintype "input"))
      (node (ref "IC29") (pin "2") (pinfunction "IN_2") (pintype "input"))
      (node (ref "IC29") (pin "3") (pinfunction "IN_3") (pintype "input"))
      (node (ref "L15") (pin "2") (pinfunction "2_2") (pintype "passive"))
    )
    (net (code "47") (name "Net-(IC18-+Vout)") (class "Default")
      (node (ref "C59") (pin "2") (pinfunction "2_2") (pintype "passive"))
      (node (ref "IC18") (pin "14") (pinfunction "+Vout_14") (pintype "power_in"))
      (node (ref "L4") (pin "1") (pinfunction "1_1") (pintype "passive"))
    )
    (net (code "48") (name "Net-(IC18--Vout)") (class "Default")
      (node (ref "C78") (pin "1") (pinfunction "1_1") (pintype "passive"))
      (node (ref "IC18") (pin "11") (pinfunction "-Vout_11") (pintype "power_in"))
      (node (ref "L9") (pin "1") (pinfunction "1_1") (pintype "passive"))
    )
    (net (code "49") (name "Net-(IC21-FB)") (class "Default")
      (node (ref "IC21") (pin "5") (pinfunction "FB_5") (pintype "input"))
      (node (ref "R66") (pin "1") (pinfunction "1_1") (pintype "passive"))
      (node (ref "R69") (pin "2") (pinfunction "2_2") (pintype "passive"))
    )
    (net (code "50") (name "Net-(IC21-RT)") (class "Default")
      (node (ref "IC21") (pin "8") (pinfunction "RT_8") (pintype "input"))
      (node (ref "R70") (pin "2") (pinfunction "2_2") (pintype "passive"))
    )
    (net (code "51") (name "Net-(IC21-SW)") (class "Default")
      (node (ref "IC21") (pin "10") (pinfunction "SW_10") (pintype "power_in"))
      (node (ref "L12") (pin "1") (pinfunction "1_1") (pintype "passive"))
    )
    (net (code "52") (name "Net-(IC21-TR{slash}SS)") (class "Default")
      (node (ref "C96") (pin "2") (pinfunction "2_2") (pintype "passive"))
      (node (ref "IC21") (pin "6") (pinfunction "TR/SS_6") (pintype "input"))
    )
    (net (code "53") (name "Net-(IC22-VOUT)") (class "Default")
      (node (ref "C99") (pin "2") (pinfunction "2_2") (pintype "passive"))
      (node (ref "IC22") (pin "5") (pinfunction "VOUT_5") (pintype "power_in"))
      (node (ref "L13") (pin "1") (pinfunction "1_1") (pintype "passive"))
    )
    (net (code "54") (name "Net-(LD1-A)") (class "Default")
      (node (ref "LD1") (pin "2") (pinfunction "A_2") (pintype "passive"))
      (node (ref "R125") (pin "1") (pinfunction "1_1") (pintype "passive"))
    )
    (net (code "55") (name "Net-(LD1-C)") (class "Default")
      (node (ref "LD1") (pin "1") (pinfunction "C_1") (pintype "passive"))
      (node (ref "T8") (pin "3") (pinfunction "D_3") (pintype "passive"))
    )
    (net (code "56") (name "Net-(LD2-A)") (class "Default")
      (node (ref "LD2") (pin "2") (pinfunction "A_2") (pintype "passive"))
      (node (ref "R126") (pin "1") (pinfunction "1_1") (pintype "passive"))
    )
    (net (code "57") (name "Net-(LD2-C)") (class "Default")
      (node (ref "LD2") (pin "1") (pinfunction "C_1") (pintype "passive"))
      (node (ref "T9") (pin "3") (pinfunction "D_3") (pintype "passive"))
    )
    (net (code "58") (name "Net-(LD3-A)") (class "Default")
      (node (ref "LD3") (pin "2") (pinfunction "A_2") (pintype "passive"))
      (node (ref "R127") (pin "1") (pinfunction "1_1") (pintype "passive"))
    )
    (net (code "59") (name "Net-(LD3-C)") (class "Default")
      (node (ref "LD3") (pin "1") (pinfunction "C_1") (pintype "passive"))
      (node (ref "T10") (pin "3") (pinfunction "D_3") (pintype "passive"))
    )
    (net (code "60") (name "Net-(LD4-A)") (class "Default")
      (node (ref "LD4") (pin "2") (pinfunction "A_2") (pintype "passive"))
      (node (ref "R128") (pin "1") (pinfunction "1_1") (pintype "passive"))
    )
    (net (code "61") (name "Net-(LD4-C)") (class "Default")
      (node (ref "LD4") (pin "1") (pinfunction "C_1") (pintype "passive"))
      (node (ref "T11") (pin "3") (pinfunction "D_3") (pintype "passive"))
    )
    (net (code "62") (name "Net-(LD5-A)") (class "Default")
      (node (ref "LD5") (pin "2") (pinfunction "A_2") (pintype "passive"))
      (node (ref "R129") (pin "1") (pinfunction "1_1") (pintype "passive"))
    )
    (net (code "63") (name "Net-(LD5-C)") (class "Default")
      (node (ref "LD5") (pin "1") (pinfunction "C_1") (pintype "passive"))
      (node (ref "T12") (pin "3") (pinfunction "D_3") (pintype "passive"))
    )
    (net (code "64") (name "Net-(LD6-A)") (class "Default")
      (node (ref "LD6") (pin "2") (pinfunction "A_2") (pintype "passive"))
      (node (ref "R130") (pin "1") (pinfunction "1_1") (pintype "passive"))
    )
    (net (code "65") (name "Net-(LD6-C)") (class "Default")
      (node (ref "LD6") (pin "1") (pinfunction "C_1") (pintype "passive"))
      (node (ref "T13") (pin "3") (pinfunction "D_3") (pintype "passive"))
    )
    (net (code "66") (name "Net-(LD7-A)") (class "Default")
      (node (ref "LD7") (pin "2") (pinfunction "A_2") (pintype "passive"))
      (node (ref "R131") (pin "1") (pinfunction "1_1") (pintype "passive"))
    )
    (net (code "67") (name "Net-(LD7-C)") (class "Default")
      (node (ref "LD7") (pin "1") (pinfunction "C_1") (pintype "passive"))
      (node (ref "T14") (pin "3") (pinfunction "D_3") (pintype "passive"))
    )
    (net (code "68") (name "Net-(R73-Pad1)") (class "Default")
      (node (ref "R73") (pin "1") (pinfunction "1_1") (pintype "passive"))
      (node (ref "R74") (pin "2") (pinfunction "2_2") (pintype "passive"))
    )
    (net (code "69") (name "Net-(R83-Pad1)") (class "Default")
      (node (ref "R83") (pin "1") (pinfunction "1_1") (pintype "passive"))
      (node (ref "R84") (pin "2") (pinfunction "2_2") (pintype "passive"))
    )
    (net (code "70") (name "Net-(R88-Pad1)") (class "Default")
      (node (ref "R88") (pin "1") (pinfunction "1_1") (pintype "passive"))
      (node (ref "R89") (pin "2") (pinfunction "2_2") (pintype "passive"))
    )
    (net (code "71") (name "Net-(R94-Pad1)") (class "Default")
      (node (ref "R94") (pin "1") (pinfunction "1_1") (pintype "passive"))
      (node (ref "R96") (pin "2") (pinfunction "2_2") (pintype "passive"))
    )
    (net (code "72") (name "Net-(R98-Pad1)") (class "Default")
      (node (ref "R98") (pin "1") (pinfunction "1_1") (pintype "passive"))
      (node (ref "R99") (pin "2") (pinfunction "2_2") (pintype "passive"))
    )
    (net (code "73") (name "Net-(T5-D)") (class "Default")
      (node (ref "R76") (pin "1") (pinfunction "1_1") (pintype "passive"))
      (node (ref "T5") (pin "3") (pinfunction "D_3") (pintype "passive"))
      (node (ref "T6") (pin "1") (pinfunction "G_1") (pintype "passive"))
    )
    (net (code "74") (name "P1V1_IO") (class "Default")
      (node (ref "C120") (pin "2") (pinfunction "2_2") (pintype "passive"))
      (node (ref "C121") (pin "2") (pinfunction "2_2") (pintype "passive"))
      (node (ref "IC28") (pin "10") (pinfunction "OUTS_10") (pintype "input"))
      (node (ref "IC28") (pin "11") (pinfunction "OUT_11") (pintype "power_in"))
      (node (ref "IC28") (pin "12") (pinfunction "OUT_12") (pintype "power_in"))
      (node (ref "R90") (pin "2") (pinfunction "2_2") (pintype "passive"))
    )
    (net (code "75") (name "P1V1_VDD") (class "Default")
      (node (ref "C113") (pin "2") (pinfunction "2_2") (pintype "passive"))
      (node (ref "C114") (pin "2") (pinfunction "2_2") (pintype "passive"))
      (node (ref "IC26") (pin "10") (pinfunction "OUTS_10") (pintype "input"))
      (node (ref "IC26") (pin "11") (pinfunction "OUT_11") (pintype "power_in"))
      (node (ref "IC26") (pin "12") (pinfunction "OUT_12") (pintype "power_in"))
      (node (ref "R85") (pin "2") (pinfunction "2_2") (pintype "passive"))
    )
    (net (code "76") (name "P3V0_REF") (class "Default")
      (node (ref "C117") (pin "2") (pinfunction "2_2") (pintype "passive"))
      (node (ref "IC27") (pin "6") (pinfunction "VOUTS_6") (pintype "power_in"))
      (node (ref "IC27") (pin "7") (pinfunction "VOUTF_7") (pintype "power_in"))
    )
    (net (code "77") (name "P3V3_ADC") (class "Default")
      (node (ref "C108") (pin "2") (pinfunction "2_2") (pintype "passive"))
      (node (ref "C109") (pin "2") (pinfunction "2_2") (pintype "passive"))
      (node (ref "IC25") (pin "10") (pinfunction "OUTS_10") (pintype "input"))
      (node (ref "IC25") (pin "11") (pinfunction "OUT_11") (pintype "power_in"))
      (node (ref "IC25") (pin "12") (pinfunction "OUT_12") (pintype "power_in"))
      (node (ref "R78") (pin "2") (pinfunction "2_2") (pintype "passive"))
    )
    (net (code "78") (name "P3V3_CLK") (class "Default")
      (node (ref "C126") (pin "2") (pinfunction "2_2") (pintype "passive"))
      (node (ref "C127") (pin "2") (pinfunction "2_2") (pintype "passive"))
      (node (ref "IC29") (pin "10") (pinfunction "OUTS_10") (pintype "input"))
      (node (ref "IC29") (pin "11") (pinfunction "OUT_11") (pintype "power_in"))
      (node (ref "IC29") (pin "12") (pinfunction "OUT_12") (pintype "power_in"))
      (node (ref "R92") (pin "2") (pinfunction "2_2") (pintype "passive"))
    )
    (net (code "79") (name "P3V6") (class "Default")
      (node (ref "C102") (pin "2") (pinfunction "2_2") (pintype "passive"))
      (node (ref "C105") (pin "2") (pinfunction "2_2") (pintype "passive"))
      (node (ref "C106") (pin "2") (pinfunction "2_2") (pintype "passive"))
      (node (ref "C110") (pin "2") (pinfunction "2_2") (pintype "passive"))
      (node (ref "C118") (pin "2") (pinfunction "2_2") (pintype "passive"))
      (node (ref "C122") (pin "2") (pinfunction "2_2") (pintype "passive"))
      (node (ref "IC24") (pin "5") (pinfunction "VCC_5") (pintype "power_in"))
      (node (ref "IC26") (pin "1") (pinfunction "IN_1") (pintype "input"))
      (node (ref "IC26") (pin "2") (pinfunction "IN_2") (pintype "input"))
      (node (ref "IC26") (pin "3") (pinfunction "IN_3") (pintype "input"))
      (node (ref "IC28") (pin "1") (pinfunction "IN_1") (pintype "input"))
      (node (ref "IC28") (pin "2") (pinfunction "IN_2") (pintype "input"))
      (node (ref "IC28") (pin "3") (pinfunction "IN_3") (pintype "input"))
      (node (ref "L14") (pin "2") (pinfunction "2_2") (pintype "passive"))
      (node (ref "L16") (pin "1") (pinfunction "1_1") (pintype "passive"))
      (node (ref "R125") (pin "2") (pinfunction "2_2") (pintype "passive"))
      (node (ref "R126") (pin "2") (pinfunction "2_2") (pintype "passive"))
      (node (ref "R127") (pin "2") (pinfunction "2_2") (pintype "passive"))
      (node (ref "R128") (pin "2") (pinfunction "2_2") (pintype "passive"))
      (node (ref "R129") (pin "2") (pinfunction "2_2") (pintype "passive"))
      (node (ref "R130") (pin "2") (pinfunction "2_2") (pintype "passive"))
      (node (ref "R131") (pin "2") (pinfunction "2_2") (pintype "passive"))
      (node (ref "R71") (pin "2") (pinfunction "2_2") (pintype "passive"))
      (node (ref "R72") (pin "2") (pinfunction "2_2") (pintype "passive"))
      (node (ref "R73") (pin "2") (pinfunction "2_2") (pintype "passive"))
      (node (ref "R76") (pin "2") (pinfunction "2_2") (pintype "passive"))
      (node (ref "R77") (pin "2") (pinfunction "2_2") (pintype "passive"))
      (node (ref "R79") (pin "2") (pinfunction "2_2") (pintype "passive"))
      (node (ref "R80") (pin "2") (pinfunction "2_2") (pintype "passive"))
    )
    (net (code "80") (name "P5V0") (class "Default")
      (node (ref "C107") (pin "2") (pinfunction "2_2") (pintype "passive"))
      (node (ref "C116") (pin "2") (pinfunction "2_2") (pintype "passive"))
      (node (ref "C83") (pin "1") (pinfunction "1_1") (pintype "passive"))
      (node (ref "C86") (pin "2") (pinfunction "2_2") (pintype "passive"))
      (node (ref "IC25") (pin "1") (pinfunction "IN_1") (pintype "input"))
      (node (ref "IC25") (pin "2") (pinfunction "IN_2") (pintype "input"))
      (node (ref "IC25") (pin "3") (pinfunction "IN_3") (pintype "input"))
      (node (ref "IC27") (pin "2") (pinfunction "VIN_2") (pintype "input"))
      (node (ref "L8") (pin "2") (pinfunction "2_2") (pintype "passive"))
      (node (ref "R61") (pin "2") (pinfunction "2_2") (pintype "passive"))
    )
    (net (code "81") (name "P12V0") (class "Default")
      (node (ref "C103") (pin "2") (pinfunction "2_2") (pintype "passive"))
      (node (ref "C104") (pin "2") (pinfunction "2_2") (pintype "passive"))
      (node (ref "C66") (pin "2") (pinfunction "2_2") (pintype "passive"))
      (node (ref "C75") (pin "2") (pinfunction "2_2") (pintype "passive"))
      (node (ref "C76") (pin "2") (pinfunction "2_2") (pintype "passive"))
      (node (ref "C77") (pin "2") (pinfunction "2_2") (pintype "passive"))
      (node (ref "C91") (pin "2") (pinfunction "2_2") (pintype "passive"))
      (node (ref "C95") (pin "2") (pinfunction "2_2") (pintype "passive"))
      (node (ref "IC19") (pin "1") (pinfunction "IN_1") (pintype "input"))
      (node (ref "IC19") (pin "2") (pinfunction "IN_2") (pintype "input"))
      (node (ref "IC19") (pin "3") (pinfunction "IN_3") (pintype "input"))
      (node (ref "IC21") (pin "1") (pinfunction "VIN_1") (pintype "power_in"))
      (node (ref "IC23") (pin "3") (pinfunction "VIN_3") (pintype "input"))
      (node (ref "L7") (pin "1") (pinfunction "1_1") (pintype "passive"))
    )
    (net (code "82") (name "P14V7_LNA") (class "Default")
      (node (ref "C64") (pin "2") (pinfunction "2_2") (pintype "passive"))
      (node (ref "C65") (pin "2") (pinfunction "2_2") (pintype "passive"))
      (node (ref "IC17") (pin "10") (pinfunction "OUTS_10") (pintype "input"))
      (node (ref "IC17") (pin "11") (pinfunction "OUT_11") (pintype "power_in"))
      (node (ref "IC17") (pin "12") (pinfunction "OUT_12") (pintype "power_in"))
    )
    (net (code "83") (name "unconnected-(IC20-VIOC-Pad7)") (class "Default")
      (node (ref "IC20") (pin "7") (pinfunction "VIOC_7") (pintype "input+no_connect"))
    )
    (net (code "84") (name "unconnected-(IC21-DNC-Pad11)") (class "Default")
      (node (ref "IC21") (pin "11") (pinfunction "DNC_11") (pintype "passive"))
    )
    (net (code "85") (name "unconnected-(IC21-HYST-Pad3)") (class "Default")
      (node (ref "IC21") (pin "3") (pinfunction "HYST_3") (pintype "input+no_connect"))
    )
    (net (code "86") (name "unconnected-(IC21-SYNC{slash}MODE-Pad7)") (class "Default")
      (node (ref "IC21") (pin "7") (pinfunction "SYNC/MODE_7") (pintype "input+no_connect"))
    )
    (net (code "87") (name "unconnected-(IC22-NC-Pad4)") (class "Default")
      (node (ref "IC22") (pin "4") (pinfunction "NC_4") (pintype "passive"))
    )
    (net (code "88") (name "unconnected-(IC23-EN-Pad5)") (class "Default")
      (node (ref "IC23") (pin "5") (pinfunction "EN_5") (pintype "input+no_connect"))
    )
  )
)
